# CFA_c.net
KiCad netlist of a schematic drawn in EAGLE
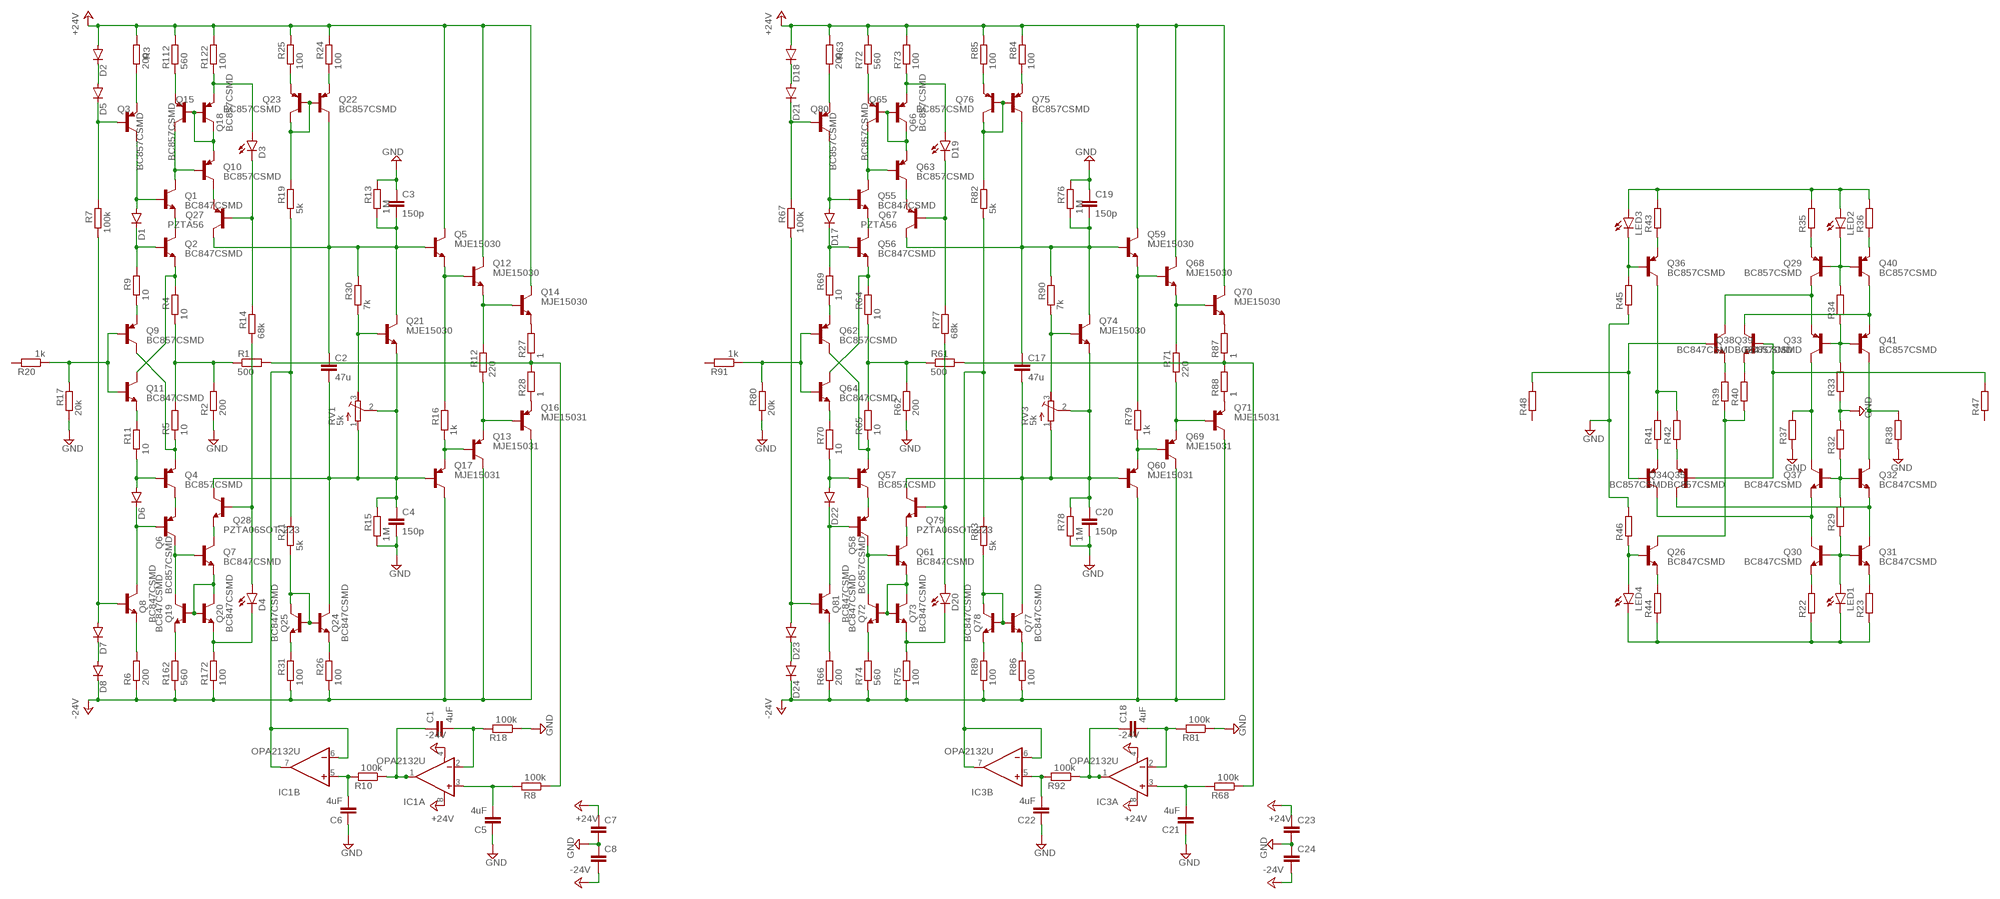
[diagram p0: schematic, sheet 1]

(export (version "E")
  (design (tool "Eeschema 10.0.6"))
  (components
    (comp (ref "C1")
      (value "4uF")
      (footprint "eagle-import:C1210")
      (fields (field (name "SPICEPREFIX") "C"))
      (libsource (lib "eagle-import") (part "C-EUC1210"))
    )
    (comp (ref "C2")
      (value "47u")
      (footprint "eagle-import:C1210")
      (fields (field (name "SPICEPREFIX") "C"))
      (libsource (lib "eagle-import") (part "C-EUC1210"))
    )
    (comp (ref "C3")
      (value "150p")
      (footprint "eagle-import:C0805")
      (fields (field (name "SPICEPREFIX") "C"))
      (libsource (lib "eagle-import") (part "C-EUC0805"))
    )
    (comp (ref "C4")
      (value "150p")
      (footprint "eagle-import:C0805")
      (fields (field (name "SPICEPREFIX") "C"))
      (libsource (lib "eagle-import") (part "C-EUC0805"))
    )
    (comp (ref "C5")
      (value "4uF")
      (footprint "eagle-import:C1210")
      (fields (field (name "SPICEPREFIX") "C"))
      (libsource (lib "eagle-import") (part "C-EUC1210"))
    )
    (comp (ref "C6")
      (value "4uF")
      (footprint "eagle-import:C1210")
      (fields (field (name "SPICEPREFIX") "C"))
      (libsource (lib "eagle-import") (part "C-EUC1210"))
    )
    (comp (ref "C7")
      (value "C-EUC0603K")
      (footprint "eagle-import:C0603K")
      (libsource (lib "eagle-import") (part "C-EUC0603K"))
    )
    (comp (ref "C8")
      (value "C-EUC0603K")
      (footprint "eagle-import:C0603K")
      (libsource (lib "eagle-import") (part "C-EUC0603K"))
    )
    (comp (ref "C17")
      (value "47u")
      (footprint "eagle-import:C1210")
      (fields (field (name "SPICEPREFIX") "C"))
      (libsource (lib "eagle-import") (part "C-EUC1210"))
    )
    (comp (ref "C18")
      (value "4uF")
      (footprint "eagle-import:C1210")
      (fields (field (name "SPICEPREFIX") "C"))
      (libsource (lib "eagle-import") (part "C-EUC1210"))
    )
    (comp (ref "C19")
      (value "150p")
      (footprint "eagle-import:C0805")
      (fields (field (name "SPICEPREFIX") "C"))
      (libsource (lib "eagle-import") (part "C-EUC0805"))
    )
    (comp (ref "C20")
      (value "150p")
      (footprint "eagle-import:C0805")
      (fields (field (name "SPICEPREFIX") "C"))
      (libsource (lib "eagle-import") (part "C-EUC0805"))
    )
    (comp (ref "C21")
      (value "4uF")
      (footprint "eagle-import:C1210")
      (fields (field (name "SPICEPREFIX") "C"))
      (libsource (lib "eagle-import") (part "C-EUC1210"))
    )
    (comp (ref "C22")
      (value "4uF")
      (footprint "eagle-import:C1210")
      (fields (field (name "SPICEPREFIX") "C"))
      (libsource (lib "eagle-import") (part "C-EUC1210"))
    )
    (comp (ref "C23")
      (value "C-EUC0603K")
      (footprint "eagle-import:C0603K")
      (libsource (lib "eagle-import") (part "C-EUC0603K"))
    )
    (comp (ref "C24")
      (value "C-EUC0603K")
      (footprint "eagle-import:C0603K")
      (libsource (lib "eagle-import") (part "C-EUC0603K"))
    )
    (comp (ref "D1")
      (value "DIODE-SOD80C")
      (footprint "eagle-import:SOD80C")
      (fields (field (name "SPICEPREFIX") "D"))
      (libsource (lib "eagle-import") (part "DIODE-SOD80C"))
    )
    (comp (ref "D2")
      (value "DIODE-SOD80C")
      (footprint "eagle-import:SOD80C")
      (fields (field (name "SPICEPREFIX") "D"))
      (libsource (lib "eagle-import") (part "DIODE-SOD80C"))
    )
    (comp (ref "D3")
      (value "LEDCHIPLED_1206")
      (footprint "eagle-import:CHIPLED_1206")
      (fields (field (name "SPICEPREFIX") "D"))
      (libsource (lib "eagle-import") (part "LEDCHIPLED_1206"))
    )
    (comp (ref "D4")
      (value "LEDCHIPLED_1206")
      (footprint "eagle-import:CHIPLED_1206")
      (fields (field (name "SPICEPREFIX") "D"))
      (libsource (lib "eagle-import") (part "LEDCHIPLED_1206"))
    )
    (comp (ref "D5")
      (value "DIODE-SOD80C")
      (footprint "eagle-import:SOD80C")
      (fields (field (name "SPICEPREFIX") "D"))
      (libsource (lib "eagle-import") (part "DIODE-SOD80C"))
    )
    (comp (ref "D6")
      (value "DIODE-SOD80C")
      (footprint "eagle-import:SOD80C")
      (fields (field (name "SPICEPREFIX") "D"))
      (libsource (lib "eagle-import") (part "DIODE-SOD80C"))
    )
    (comp (ref "D7")
      (value "DIODE-SOD80C")
      (footprint "eagle-import:SOD80C")
      (fields (field (name "SPICEPREFIX") "D"))
      (libsource (lib "eagle-import") (part "DIODE-SOD80C"))
    )
    (comp (ref "D8")
      (value "DIODE-SOD80C")
      (footprint "eagle-import:SOD80C")
      (fields (field (name "SPICEPREFIX") "D"))
      (libsource (lib "eagle-import") (part "DIODE-SOD80C"))
    )
    (comp (ref "D17")
      (value "DIODE-SOD80C")
      (footprint "eagle-import:SOD80C")
      (fields (field (name "SPICEPREFIX") "D"))
      (libsource (lib "eagle-import") (part "DIODE-SOD80C"))
    )
    (comp (ref "D18")
      (value "DIODE-SOD80C")
      (footprint "eagle-import:SOD80C")
      (fields (field (name "SPICEPREFIX") "D"))
      (libsource (lib "eagle-import") (part "DIODE-SOD80C"))
    )
    (comp (ref "D19")
      (value "LEDCHIPLED_1206")
      (footprint "eagle-import:CHIPLED_1206")
      (fields (field (name "SPICEPREFIX") "D"))
      (libsource (lib "eagle-import") (part "LEDCHIPLED_1206"))
    )
    (comp (ref "D20")
      (value "LEDCHIPLED_1206")
      (footprint "eagle-import:CHIPLED_1206")
      (fields (field (name "SPICEPREFIX") "D"))
      (libsource (lib "eagle-import") (part "LEDCHIPLED_1206"))
    )
    (comp (ref "D21")
      (value "DIODE-SOD80C")
      (footprint "eagle-import:SOD80C")
      (fields (field (name "SPICEPREFIX") "D"))
      (libsource (lib "eagle-import") (part "DIODE-SOD80C"))
    )
    (comp (ref "D22")
      (value "DIODE-SOD80C")
      (footprint "eagle-import:SOD80C")
      (fields (field (name "SPICEPREFIX") "D"))
      (libsource (lib "eagle-import") (part "DIODE-SOD80C"))
    )
    (comp (ref "D23")
      (value "DIODE-SOD80C")
      (footprint "eagle-import:SOD80C")
      (fields (field (name "SPICEPREFIX") "D"))
      (libsource (lib "eagle-import") (part "DIODE-SOD80C"))
    )
    (comp (ref "D24")
      (value "DIODE-SOD80C")
      (footprint "eagle-import:SOD80C")
      (fields (field (name "SPICEPREFIX") "D"))
      (libsource (lib "eagle-import") (part "DIODE-SOD80C"))
    )
    (comp (ref "IC1")
      (value "OPA2132U")
      (footprint "eagle-import:SO08")
      (fields (field (name "MF") "TEXAS INSTRUMENTS"))
      (libsource (lib "eagle-import") (part "OPA2132U"))
    )
    (comp (ref "IC3")
      (value "OPA2132U")
      (footprint "eagle-import:SO08")
      (fields (field (name "MF") "TEXAS INSTRUMENTS"))
      (libsource (lib "eagle-import") (part "OPA2132U"))
    )
    (comp (ref "LED1")
      (value "LEDCHIPLED_1206")
      (footprint "eagle-import:CHIPLED_1206")
      (libsource (lib "eagle-import") (part "LEDCHIPLED_1206"))
    )
    (comp (ref "LED2")
      (value "LEDCHIPLED_1206")
      (footprint "eagle-import:CHIPLED_1206")
      (libsource (lib "eagle-import") (part "LEDCHIPLED_1206"))
    )
    (comp (ref "LED3")
      (value "LEDCHIPLED_1206")
      (footprint "eagle-import:CHIPLED_1206")
      (libsource (lib "eagle-import") (part "LEDCHIPLED_1206"))
    )
    (comp (ref "LED4")
      (value "LEDCHIPLED_1206")
      (footprint "eagle-import:CHIPLED_1206")
      (fields (field (name "SPICEPREFIX") "D"))
      (libsource (lib "eagle-import") (part "LEDCHIPLED_1206"))
    )
    (comp (ref "Q1")
      (value "BC847CSMD")
      (footprint "eagle-import:SOT23")
      (fields (field (name "SPICEPREFIX") "Q"))
      (libsource (lib "eagle-import") (part "BC847SMDC"))
    )
    (comp (ref "Q2")
      (value "BC847CSMD")
      (footprint "eagle-import:SOT23")
      (fields (field (name "SPICEPREFIX") "Q"))
      (libsource (lib "eagle-import") (part "BC847SMDC"))
    )
    (comp (ref "Q3")
      (value "BC857CSMD")
      (footprint "eagle-import:SOT23-BEC")
      (fields (field (name "SPICEPREFIX") "Q"))
      (libsource (lib "eagle-import") (part "BC857SMDC"))
    )
    (comp (ref "Q4")
      (value "BC857CSMD")
      (footprint "eagle-import:SOT23-BEC")
      (fields (field (name "SPICEPREFIX") "Q"))
      (libsource (lib "eagle-import") (part "BC857SMDC"))
    )
    (comp (ref "Q5")
      (value "MJE15030")
      (footprint "eagle-import:DPAK")
      (fields (field (name "SPICEPREFIX") "Q"))
      (libsource (lib "eagle-import") (part "MJD31C"))
    )
    (comp (ref "Q6")
      (value "BC857CSMD")
      (footprint "eagle-import:SOT23-BEC")
      (fields (field (name "SPICEPREFIX") "Q"))
      (libsource (lib "eagle-import") (part "BC857SMDC"))
    )
    (comp (ref "Q7")
      (value "BC847CSMD")
      (footprint "eagle-import:SOT23")
      (fields (field (name "SPICEPREFIX") "Q"))
      (libsource (lib "eagle-import") (part "BC847SMDC"))
    )
    (comp (ref "Q8")
      (value "BC847CSMD")
      (footprint "eagle-import:SOT23")
      (fields (field (name "SPICEPREFIX") "Q"))
      (libsource (lib "eagle-import") (part "BC847SMDC"))
    )
    (comp (ref "Q9")
      (value "BC857CSMD")
      (footprint "eagle-import:SOT23-BEC")
      (fields (field (name "SPICEPREFIX") "Q"))
      (libsource (lib "eagle-import") (part "BC857SMDC"))
    )
    (comp (ref "Q10")
      (value "BC857CSMD")
      (footprint "eagle-import:SOT23-BEC")
      (fields (field (name "SPICEPREFIX") "Q"))
      (libsource (lib "eagle-import") (part "BC857SMDC"))
    )
    (comp (ref "Q11")
      (value "BC847CSMD")
      (footprint "eagle-import:SOT23")
      (fields (field (name "SPICEPREFIX") "Q"))
      (libsource (lib "eagle-import") (part "BC847SMDC"))
    )
    (comp (ref "Q12")
      (value "MJE15030")
      (footprint "eagle-import:DPAK")
      (fields (field (name "SPICEPREFIX") "Q"))
      (libsource (lib "eagle-import") (part "MJD31C"))
    )
    (comp (ref "Q13")
      (value "MJE15031")
      (footprint "eagle-import:DPAK")
      (fields (field (name "SPICEPREFIX") "Q"))
      (libsource (lib "eagle-import") (part "MJD32C"))
    )
    (comp (ref "Q14")
      (value "MJE15030")
      (footprint "eagle-import:DPAK")
      (fields (field (name "SPICEPREFIX") "Q"))
      (libsource (lib "eagle-import") (part "MJD31C"))
    )
    (comp (ref "Q15")
      (value "BC857CSMD")
      (footprint "eagle-import:SOT23-BEC")
      (fields (field (name "SPICEPREFIX") "Q"))
      (libsource (lib "eagle-import") (part "BC857SMDC"))
    )
    (comp (ref "Q16")
      (value "MJE15031")
      (footprint "eagle-import:DPAK")
      (fields (field (name "SPICEPREFIX") "Q"))
      (libsource (lib "eagle-import") (part "MJD32C"))
    )
    (comp (ref "Q17")
      (value "MJE15031")
      (footprint "eagle-import:DPAK")
      (fields (field (name "SPICEPREFIX") "Q"))
      (libsource (lib "eagle-import") (part "MJD32C"))
    )
    (comp (ref "Q18")
      (value "BC857CSMD")
      (footprint "eagle-import:SOT23-BEC")
      (fields (field (name "SPICEPREFIX") "Q"))
      (libsource (lib "eagle-import") (part "BC857SMDC"))
    )
    (comp (ref "Q19")
      (value "BC847CSMD")
      (footprint "eagle-import:SOT23")
      (fields (field (name "SPICEPREFIX") "Q"))
      (libsource (lib "eagle-import") (part "BC847SMDC"))
    )
    (comp (ref "Q20")
      (value "BC847CSMD")
      (footprint "eagle-import:SOT23")
      (fields (field (name "SPICEPREFIX") "Q"))
      (libsource (lib "eagle-import") (part "BC847SMDC"))
    )
    (comp (ref "Q21")
      (value "MJE15030")
      (footprint "eagle-import:DPAK")
      (fields (field (name "SPICEPREFIX") "Q"))
      (libsource (lib "eagle-import") (part "MJD31C"))
    )
    (comp (ref "Q22")
      (value "BC857CSMD")
      (footprint "eagle-import:SOT23-BEC")
      (fields (field (name "SPICEPREFIX") "Q"))
      (libsource (lib "eagle-import") (part "BC857SMDC"))
    )
    (comp (ref "Q23")
      (value "BC857CSMD")
      (footprint "eagle-import:SOT23-BEC")
      (fields (field (name "SPICEPREFIX") "Q"))
      (libsource (lib "eagle-import") (part "BC857SMDC"))
    )
    (comp (ref "Q24")
      (value "BC847CSMD")
      (footprint "eagle-import:SOT23")
      (fields (field (name "SPICEPREFIX") "Q"))
      (libsource (lib "eagle-import") (part "BC847SMDC"))
    )
    (comp (ref "Q25")
      (value "BC847CSMD")
      (footprint "eagle-import:SOT23")
      (fields (field (name "SPICEPREFIX") "Q"))
      (libsource (lib "eagle-import") (part "BC847SMDC"))
    )
    (comp (ref "Q26")
      (value "BC847CSMD")
      (footprint "eagle-import:SOT23")
      (fields (field (name "SPICEPREFIX") "Q"))
      (libsource (lib "eagle-import") (part "BC847SMDC"))
    )
    (comp (ref "Q27")
      (value "PZTA56")
      (footprint "eagle-import:SOT223")
      (fields (field (name "SPICEPREFIX") "Q"))
      (libsource (lib "eagle-import") (part "PZTA56"))
    )
    (comp (ref "Q28")
      (value "PZTA06SOT-223")
      (footprint "eagle-import:SOT223")
      (fields (field (name "SPICEPREFIX") "Q"))
      (libsource (lib "eagle-import") (part "PZTA06SOT-223"))
    )
    (comp (ref "Q29")
      (value "BC857CSMD")
      (footprint "eagle-import:SOT23-BEC")
      (fields (field (name "SPICEPREFIX") "Q"))
      (libsource (lib "eagle-import") (part "BC857SMDC"))
    )
    (comp (ref "Q30")
      (value "BC847CSMD")
      (footprint "eagle-import:SOT23")
      (fields (field (name "SPICEPREFIX") "Q"))
      (libsource (lib "eagle-import") (part "BC847SMDC"))
    )
    (comp (ref "Q31")
      (value "BC847CSMD")
      (footprint "eagle-import:SOT23")
      (fields (field (name "SPICEPREFIX") "Q"))
      (libsource (lib "eagle-import") (part "BC847SMDC"))
    )
    (comp (ref "Q32")
      (value "BC847CSMD")
      (footprint "eagle-import:SOT23")
      (fields (field (name "SPICEPREFIX") "Q"))
      (libsource (lib "eagle-import") (part "BC847SMDC"))
    )
    (comp (ref "Q33")
      (value "BC857CSMD")
      (footprint "eagle-import:SOT23-BEC")
      (fields (field (name "SPICEPREFIX") "Q"))
      (libsource (lib "eagle-import") (part "BC857SMDC"))
    )
    (comp (ref "Q34")
      (value "BC857CSMD")
      (footprint "eagle-import:SOT23-BEC")
      (fields (field (name "SPICEPREFIX") "Q"))
      (libsource (lib "eagle-import") (part "BC857SMDC"))
    )
    (comp (ref "Q35")
      (value "BC857CSMD")
      (footprint "eagle-import:SOT23-BEC")
      (fields (field (name "SPICEPREFIX") "Q"))
      (libsource (lib "eagle-import") (part "BC857SMDC"))
    )
    (comp (ref "Q36")
      (value "BC857CSMD")
      (footprint "eagle-import:SOT23-BEC")
      (fields (field (name "SPICEPREFIX") "Q"))
      (libsource (lib "eagle-import") (part "BC857SMDC"))
    )
    (comp (ref "Q37")
      (value "BC847CSMD")
      (footprint "eagle-import:SOT23")
      (fields (field (name "SPICEPREFIX") "Q"))
      (libsource (lib "eagle-import") (part "BC847SMDC"))
    )
    (comp (ref "Q38")
      (value "BC847CSMD")
      (footprint "eagle-import:SOT23")
      (fields (field (name "SPICEPREFIX") "Q"))
      (libsource (lib "eagle-import") (part "BC847SMDC"))
    )
    (comp (ref "Q39")
      (value "BC847CSMD")
      (footprint "eagle-import:SOT23")
      (fields (field (name "SPICEPREFIX") "Q"))
      (libsource (lib "eagle-import") (part "BC847SMDC"))
    )
    (comp (ref "Q40")
      (value "BC857CSMD")
      (footprint "eagle-import:SOT23-BEC")
      (fields (field (name "SPICEPREFIX") "Q"))
      (libsource (lib "eagle-import") (part "BC857SMDC"))
    )
    (comp (ref "Q41")
      (value "BC857CSMD")
      (footprint "eagle-import:SOT23-BEC")
      (fields (field (name "SPICEPREFIX") "Q"))
      (libsource (lib "eagle-import") (part "BC857SMDC"))
    )
    (comp (ref "Q55")
      (value "BC847CSMD")
      (footprint "eagle-import:SOT23")
      (fields (field (name "SPICEPREFIX") "Q"))
      (libsource (lib "eagle-import") (part "BC847SMDC"))
    )
    (comp (ref "Q56")
      (value "BC847CSMD")
      (footprint "eagle-import:SOT23")
      (fields (field (name "SPICEPREFIX") "Q"))
      (libsource (lib "eagle-import") (part "BC847SMDC"))
    )
    (comp (ref "Q57")
      (value "BC857CSMD")
      (footprint "eagle-import:SOT23-BEC")
      (fields (field (name "SPICEPREFIX") "Q"))
      (libsource (lib "eagle-import") (part "BC857SMDC"))
    )
    (comp (ref "Q58")
      (value "BC857CSMD")
      (footprint "eagle-import:SOT23-BEC")
      (fields (field (name "SPICEPREFIX") "Q"))
      (libsource (lib "eagle-import") (part "BC857SMDC"))
    )
    (comp (ref "Q59")
      (value "MJE15030")
      (footprint "eagle-import:DPAK")
      (fields (field (name "SPICEPREFIX") "Q"))
      (libsource (lib "eagle-import") (part "MJD31C"))
    )
    (comp (ref "Q60")
      (value "MJE15031")
      (footprint "eagle-import:DPAK")
      (fields (field (name "SPICEPREFIX") "Q"))
      (libsource (lib "eagle-import") (part "MJD32C"))
    )
    (comp (ref "Q61")
      (value "BC847CSMD")
      (footprint "eagle-import:SOT23")
      (fields (field (name "SPICEPREFIX") "Q"))
      (libsource (lib "eagle-import") (part "BC847SMDC"))
    )
    (comp (ref "Q62")
      (value "BC857CSMD")
      (footprint "eagle-import:SOT23-BEC")
      (fields (field (name "SPICEPREFIX") "Q"))
      (libsource (lib "eagle-import") (part "BC857SMDC"))
    )
    (comp (ref "Q63")
      (value "BC857CSMD")
      (footprint "eagle-import:SOT23-BEC")
      (fields (field (name "SPICEPREFIX") "Q"))
      (libsource (lib "eagle-import") (part "BC857SMDC"))
    )
    (comp (ref "Q64")
      (value "BC847CSMD")
      (footprint "eagle-import:SOT23")
      (fields (field (name "SPICEPREFIX") "Q"))
      (libsource (lib "eagle-import") (part "BC847SMDC"))
    )
    (comp (ref "Q65")
      (value "BC857CSMD")
      (footprint "eagle-import:SOT23-BEC")
      (fields (field (name "SPICEPREFIX") "Q"))
      (libsource (lib "eagle-import") (part "BC857SMDC"))
    )
    (comp (ref "Q66")
      (value "BC857CSMD")
      (footprint "eagle-import:SOT23-BEC")
      (fields (field (name "SPICEPREFIX") "Q"))
      (libsource (lib "eagle-import") (part "BC857SMDC"))
    )
    (comp (ref "Q67")
      (value "PZTA56")
      (footprint "eagle-import:SOT223")
      (fields (field (name "SPICEPREFIX") "Q"))
      (libsource (lib "eagle-import") (part "PZTA56"))
    )
    (comp (ref "Q68")
      (value "MJE15030")
      (footprint "eagle-import:DPAK")
      (fields (field (name "SPICEPREFIX") "Q"))
      (libsource (lib "eagle-import") (part "MJD31C"))
    )
    (comp (ref "Q69")
      (value "MJE15031")
      (footprint "eagle-import:DPAK")
      (fields (field (name "SPICEPREFIX") "Q"))
      (libsource (lib "eagle-import") (part "MJD32C"))
    )
    (comp (ref "Q70")
      (value "MJE15030")
      (footprint "eagle-import:DPAK")
      (fields (field (name "SPICEPREFIX") "Q"))
      (libsource (lib "eagle-import") (part "MJD31C"))
    )
    (comp (ref "Q71")
      (value "MJE15031")
      (footprint "eagle-import:DPAK")
      (fields (field (name "SPICEPREFIX") "Q"))
      (libsource (lib "eagle-import") (part "MJD32C"))
    )
    (comp (ref "Q72")
      (value "BC847CSMD")
      (footprint "eagle-import:SOT23")
      (fields (field (name "SPICEPREFIX") "Q"))
      (libsource (lib "eagle-import") (part "BC847SMDC"))
    )
    (comp (ref "Q73")
      (value "BC847CSMD")
      (footprint "eagle-import:SOT23")
      (fields (field (name "SPICEPREFIX") "Q"))
      (libsource (lib "eagle-import") (part "BC847SMDC"))
    )
    (comp (ref "Q74")
      (value "MJE15030")
      (footprint "eagle-import:DPAK")
      (fields (field (name "SPICEPREFIX") "Q"))
      (libsource (lib "eagle-import") (part "MJD31C"))
    )
    (comp (ref "Q75")
      (value "BC857CSMD")
      (footprint "eagle-import:SOT23-BEC")
      (fields (field (name "SPICEPREFIX") "Q"))
      (libsource (lib "eagle-import") (part "BC857SMDC"))
    )
    (comp (ref "Q76")
      (value "BC857CSMD")
      (footprint "eagle-import:SOT23-BEC")
      (fields (field (name "SPICEPREFIX") "Q"))
      (libsource (lib "eagle-import") (part "BC857SMDC"))
    )
    (comp (ref "Q77")
      (value "BC847CSMD")
      (footprint "eagle-import:SOT23")
      (fields (field (name "SPICEPREFIX") "Q"))
      (libsource (lib "eagle-import") (part "BC847SMDC"))
    )
    (comp (ref "Q78")
      (value "BC847CSMD")
      (footprint "eagle-import:SOT23")
      (fields (field (name "SPICEPREFIX") "Q"))
      (libsource (lib "eagle-import") (part "BC847SMDC"))
    )
    (comp (ref "Q79")
      (value "PZTA06SOT-223")
      (footprint "eagle-import:SOT223")
      (fields (field (name "SPICEPREFIX") "Q"))
      (libsource (lib "eagle-import") (part "PZTA06SOT-223"))
    )
    (comp (ref "Q80")
      (value "BC857CSMD")
      (footprint "eagle-import:SOT23-BEC")
      (fields (field (name "SPICEPREFIX") "Q"))
      (libsource (lib "eagle-import") (part "BC857SMDC"))
    )
    (comp (ref "Q81")
      (value "BC847CSMD")
      (footprint "eagle-import:SOT23")
      (fields (field (name "SPICEPREFIX") "Q"))
      (libsource (lib "eagle-import") (part "BC847SMDC"))
    )
    (comp (ref "R1")
      (value "500")
      (footprint "eagle-import:MINI_MELF-0204W")
      (fields (field (name "SPICEPREFIX") "R"))
      (libsource (lib "eagle-import") (part "R-EU_MELF0204W"))
    )
    (comp (ref "R2")
      (value "200")
      (footprint "eagle-import:MINI_MELF-0204W")
      (fields (field (name "SPICEPREFIX") "R"))
      (libsource (lib "eagle-import") (part "R-EU_MELF0204W"))
    )
    (comp (ref "R3")
      (value "200")
      (footprint "eagle-import:MINI_MELF-0204W")
      (fields (field (name "SPICEPREFIX") "R"))
      (libsource (lib "eagle-import") (part "R-EU_MELF0204W"))
    )
    (comp (ref "R4")
      (value "10")
      (footprint "eagle-import:MINI_MELF-0204W")
      (fields (field (name "SPICEPREFIX") "R"))
      (libsource (lib "eagle-import") (part "R-EU_MELF0204W"))
    )
    (comp (ref "R5")
      (value "10")
      (footprint "eagle-import:MINI_MELF-0204W")
      (fields (field (name "SPICEPREFIX") "R"))
      (libsource (lib "eagle-import") (part "R-EU_MELF0204W"))
    )
    (comp (ref "R6")
      (value "200")
      (footprint "eagle-import:MINI_MELF-0204W")
      (fields (field (name "SPICEPREFIX") "R"))
      (libsource (lib "eagle-import") (part "R-EU_MELF0204W"))
    )
    (comp (ref "R7")
      (value "100k")
      (footprint "eagle-import:MINI_MELF-0204W")
      (fields (field (name "SPICEPREFIX") "R"))
      (libsource (lib "eagle-import") (part "R-EU_MELF0204W"))
    )
    (comp (ref "R8")
      (value "100k")
      (footprint "eagle-import:MINI_MELF-0204W")
      (fields (field (name "SPICEPREFIX") "R"))
      (libsource (lib "eagle-import") (part "R-EU_MELF0204W"))
    )
    (comp (ref "R9")
      (value "10")
      (footprint "eagle-import:MINI_MELF-0204W")
      (fields (field (name "SPICEPREFIX") "R"))
      (libsource (lib "eagle-import") (part "R-EU_MELF0204W"))
    )
    (comp (ref "R10")
      (value "100k")
      (footprint "eagle-import:MINI_MELF-0204W")
      (fields (field (name "SPICEPREFIX") "R"))
      (libsource (lib "eagle-import") (part "R-EU_MELF0204W"))
    )
    (comp (ref "R11")
      (value "10")
      (footprint "eagle-import:MINI_MELF-0204W")
      (fields (field (name "SPICEPREFIX") "R"))
      (libsource (lib "eagle-import") (part "R-EU_MELF0204W"))
    )
    (comp (ref "R12")
      (value "220")
      (footprint "eagle-import:MINI_MELF-0204W")
      (fields (field (name "SPICEPREFIX") "R"))
      (libsource (lib "eagle-import") (part "R-EU_MELF0204W"))
    )
    (comp (ref "R13")
      (value "1M")
      (footprint "eagle-import:MINI_MELF-0204W")
      (fields (field (name "SPICEPREFIX") "R"))
      (libsource (lib "eagle-import") (part "R-EU_MELF0204W"))
    )
    (comp (ref "R14")
      (value "68k")
      (footprint "eagle-import:MINI_MELF-0204W")
      (fields (field (name "SPICEPREFIX") "R"))
      (libsource (lib "eagle-import") (part "R-EU_MELF0204W"))
    )
    (comp (ref "R15")
      (value "1M")
      (footprint "eagle-import:MINI_MELF-0204W")
      (fields (field (name "SPICEPREFIX") "R"))
      (libsource (lib "eagle-import") (part "R-EU_MELF0204W"))
    )
    (comp (ref "R16")
      (value "1k")
      (footprint "eagle-import:MINI_MELF-0204W")
      (fields (field (name "SPICEPREFIX") "R"))
      (libsource (lib "eagle-import") (part "R-EU_MELF0204W"))
    )
    (comp (ref "R17")
      (value "20k")
      (footprint "eagle-import:MINI_MELF-0204W")
      (fields (field (name "SPICEPREFIX") "R"))
      (libsource (lib "eagle-import") (part "R-EU_MELF0204W"))
    )
    (comp (ref "R18")
      (value "100k")
      (footprint "eagle-import:MINI_MELF-0204W")
      (fields (field (name "SPICEPREFIX") "R"))
      (libsource (lib "eagle-import") (part "R-EU_MELF0204W"))
    )
    (comp (ref "R19")
      (value "5k")
      (footprint "eagle-import:MINI_MELF-0204W")
      (fields (field (name "SPICEPREFIX") "R"))
      (libsource (lib "eagle-import") (part "R-EU_MELF0204W"))
    )
    (comp (ref "R20")
      (value "1k")
      (footprint "eagle-import:MINI_MELF-0204W")
      (fields (field (name "SPICEPREFIX") "R"))
      (libsource (lib "eagle-import") (part "R-EU_MELF0204W"))
    )
    (comp (ref "R21")
      (value "5k")
      (footprint "eagle-import:MINI_MELF-0204W")
      (fields (field (name "SPICEPREFIX") "R"))
      (libsource (lib "eagle-import") (part "R-EU_MELF0204W"))
    )
    (comp (ref "R22")
      (value "R-EU_MELF0204W")
      (footprint "eagle-import:MINI_MELF-0204W")
      (libsource (lib "eagle-import") (part "R-EU_MELF0204W"))
    )
    (comp (ref "R23")
      (value "R-EU_MELF0204W")
      (footprint "eagle-import:MINI_MELF-0204W")
      (libsource (lib "eagle-import") (part "R-EU_MELF0204W"))
    )
    (comp (ref "R24")
      (value "100")
      (footprint "eagle-import:MINI_MELF-0204W")
      (fields (field (name "SPICEPREFIX") "R"))
      (libsource (lib "eagle-import") (part "R-EU_MELF0204W"))
    )
    (comp (ref "R25")
      (value "100")
      (footprint "eagle-import:MINI_MELF-0204W")
      (fields (field (name "SPICEPREFIX") "R"))
      (libsource (lib "eagle-import") (part "R-EU_MELF0204W"))
    )
    (comp (ref "R26")
      (value "100")
      (footprint "eagle-import:MINI_MELF-0204W")
      (fields (field (name "SPICEPREFIX") "R"))
      (libsource (lib "eagle-import") (part "R-EU_MELF0204W"))
    )
    (comp (ref "R27")
      (value "1")
      (footprint "eagle-import:R4527")
      (fields (field (name "SPICEPREFIX") "R"))
      (libsource (lib "eagle-import") (part "R-EU_R4527"))
    )
    (comp (ref "R28")
      (value "1")
      (footprint "eagle-import:R4527")
      (fields (field (name "SPICEPREFIX") "R"))
      (libsource (lib "eagle-import") (part "R-EU_R4527"))
    )
    (comp (ref "R29")
      (value "R-EU_MELF0204W")
      (footprint "eagle-import:MINI_MELF-0204W")
      (libsource (lib "eagle-import") (part "R-EU_MELF0204W"))
    )
    (comp (ref "R30")
      (value "7k")
      (footprint "eagle-import:MINI_MELF-0204W")
      (fields (field (name "SPICEPREFIX") "R"))
      (libsource (lib "eagle-import") (part "R-EU_MELF0204W"))
    )
    (comp (ref "R31")
      (value "100")
      (footprint "eagle-import:MINI_MELF-0204W")
      (fields (field (name "SPICEPREFIX") "R"))
      (libsource (lib "eagle-import") (part "R-EU_MELF0204W"))
    )
    (comp (ref "R32")
      (value "R-EU_MELF0204W")
      (footprint "eagle-import:MINI_MELF-0204W")
      (libsource (lib "eagle-import") (part "R-EU_MELF0204W"))
    )
    (comp (ref "R33")
      (value "R-EU_MELF0204W")
      (footprint "eagle-import:MINI_MELF-0204W")
      (libsource (lib "eagle-import") (part "R-EU_MELF0204W"))
    )
    (comp (ref "R34")
      (value "R-EU_MELF0204W")
      (footprint "eagle-import:MINI_MELF-0204W")
      (libsource (lib "eagle-import") (part "R-EU_MELF0204W"))
    )
    (comp (ref "R35")
      (value "R-EU_MELF0204W")
      (footprint "eagle-import:MINI_MELF-0204W")
      (libsource (lib "eagle-import") (part "R-EU_MELF0204W"))
    )
    (comp (ref "R36")
      (value "R-EU_MELF0204W")
      (footprint "eagle-import:MINI_MELF-0204W")
      (libsource (lib "eagle-import") (part "R-EU_MELF0204W"))
    )
    (comp (ref "R37")
      (value "R-EU_MELF0204W")
      (footprint "eagle-import:MINI_MELF-0204W")
      (libsource (lib "eagle-import") (part "R-EU_MELF0204W"))
    )
    (comp (ref "R38")
      (value "R-EU_MELF0204W")
      (footprint "eagle-import:MINI_MELF-0204W")
      (libsource (lib "eagle-import") (part "R-EU_MELF0204W"))
    )
    (comp (ref "R39")
      (value "R-EU_MELF0204W")
      (footprint "eagle-import:MINI_MELF-0204W")
      (libsource (lib "eagle-import") (part "R-EU_MELF0204W"))
    )
    (comp (ref "R40")
      (value "R-EU_MELF0204W")
      (footprint "eagle-import:MINI_MELF-0204W")
      (libsource (lib "eagle-import") (part "R-EU_MELF0204W"))
    )
    (comp (ref "R41")
      (value "R-EU_MELF0204W")
      (footprint "eagle-import:MINI_MELF-0204W")
      (libsource (lib "eagle-import") (part "R-EU_MELF0204W"))
    )
    (comp (ref "R42")
      (value "R-EU_MELF0204W")
      (footprint "eagle-import:MINI_MELF-0204W")
      (libsource (lib "eagle-import") (part "R-EU_MELF0204W"))
    )
    (comp (ref "R43")
      (value "R-EU_MELF0204W")
      (footprint "eagle-import:MINI_MELF-0204W")
      (libsource (lib "eagle-import") (part "R-EU_MELF0204W"))
    )
    (comp (ref "R44")
      (value "R-EU_MELF0204W")
      (footprint "eagle-import:MINI_MELF-0204W")
      (fields (field (name "SPICEPREFIX") "R"))
      (libsource (lib "eagle-import") (part "R-EU_MELF0204W"))
    )
    (comp (ref "R45")
      (value "R-EU_MELF0204W")
      (footprint "eagle-import:MINI_MELF-0204W")
      (libsource (lib "eagle-import") (part "R-EU_MELF0204W"))
    )
    (comp (ref "R46")
      (value "R-EU_MELF0204W")
      (footprint "eagle-import:MINI_MELF-0204W")
      (libsource (lib "eagle-import") (part "R-EU_MELF0204W"))
    )
    (comp (ref "R47")
      (value "R-EU_MELF0204W")
      (footprint "eagle-import:MINI_MELF-0204W")
      (libsource (lib "eagle-import") (part "R-EU_MELF0204W"))
    )
    (comp (ref "R48")
      (value "R-EU_MELF0204W")
      (footprint "eagle-import:MINI_MELF-0204W")
      (libsource (lib "eagle-import") (part "R-EU_MELF0204W"))
    )
    (comp (ref "R61")
      (value "500")
      (footprint "eagle-import:MINI_MELF-0204W")
      (fields (field (name "SPICEPREFIX") "R"))
      (libsource (lib "eagle-import") (part "R-EU_MELF0204W"))
    )
    (comp (ref "R62")
      (value "200")
      (footprint "eagle-import:MINI_MELF-0204W")
      (fields (field (name "SPICEPREFIX") "R"))
      (libsource (lib "eagle-import") (part "R-EU_MELF0204W"))
    )
    (comp (ref "R63")
      (value "200")
      (footprint "eagle-import:MINI_MELF-0204W")
      (fields (field (name "SPICEPREFIX") "R"))
      (libsource (lib "eagle-import") (part "R-EU_MELF0204W"))
    )
    (comp (ref "R64")
      (value "10")
      (footprint "eagle-import:MINI_MELF-0204W")
      (fields (field (name "SPICEPREFIX") "R"))
      (libsource (lib "eagle-import") (part "R-EU_MELF0204W"))
    )
    (comp (ref "R65")
      (value "10")
      (footprint "eagle-import:MINI_MELF-0204W")
      (fields (field (name "SPICEPREFIX") "R"))
      (libsource (lib "eagle-import") (part "R-EU_MELF0204W"))
    )
    (comp (ref "R66")
      (value "200")
      (footprint "eagle-import:MINI_MELF-0204W")
      (fields (field (name "SPICEPREFIX") "R"))
      (libsource (lib "eagle-import") (part "R-EU_MELF0204W"))
    )
    (comp (ref "R67")
      (value "100k")
      (footprint "eagle-import:MINI_MELF-0204W")
      (fields (field (name "SPICEPREFIX") "R"))
      (libsource (lib "eagle-import") (part "R-EU_MELF0204W"))
    )
    (comp (ref "R68")
      (value "100k")
      (footprint "eagle-import:MINI_MELF-0204W")
      (fields (field (name "SPICEPREFIX") "R"))
      (libsource (lib "eagle-import") (part "R-EU_MELF0204W"))
    )
    (comp (ref "R69")
      (value "10")
      (footprint "eagle-import:MINI_MELF-0204W")
      (fields (field (name "SPICEPREFIX") "R"))
      (libsource (lib "eagle-import") (part "R-EU_MELF0204W"))
    )
    (comp (ref "R70")
      (value "10")
      (footprint "eagle-import:MINI_MELF-0204W")
      (fields (field (name "SPICEPREFIX") "R"))
      (libsource (lib "eagle-import") (part "R-EU_MELF0204W"))
    )
    (comp (ref "R71")
      (value "220")
      (footprint "eagle-import:MINI_MELF-0204W")
      (fields (field (name "SPICEPREFIX") "R"))
      (libsource (lib "eagle-import") (part "R-EU_MELF0204W"))
    )
    (comp (ref "R72")
      (value "560")
      (footprint "eagle-import:MINI_MELF-0204W")
      (fields (field (name "SPICEPREFIX") "R"))
      (libsource (lib "eagle-import") (part "R-EU_MELF0204W"))
    )
    (comp (ref "R73")
      (value "100")
      (footprint "eagle-import:MINI_MELF-0204W")
      (fields (field (name "SPICEPREFIX") "R"))
      (libsource (lib "eagle-import") (part "R-EU_MELF0204W"))
    )
    (comp (ref "R74")
      (value "560")
      (footprint "eagle-import:MINI_MELF-0204W")
      (fields (field (name "SPICEPREFIX") "R"))
      (libsource (lib "eagle-import") (part "R-EU_MELF0204W"))
    )
    (comp (ref "R75")
      (value "100")
      (footprint "eagle-import:MINI_MELF-0204W")
      (fields (field (name "SPICEPREFIX") "R"))
      (libsource (lib "eagle-import") (part "R-EU_MELF0204W"))
    )
    (comp (ref "R76")
      (value "1M")
      (footprint "eagle-import:MINI_MELF-0204W")
      (fields (field (name "SPICEPREFIX") "R"))
      (libsource (lib "eagle-import") (part "R-EU_MELF0204W"))
    )
    (comp (ref "R77")
      (value "68k")
      (footprint "eagle-import:MINI_MELF-0204W")
      (fields (field (name "SPICEPREFIX") "R"))
      (libsource (lib "eagle-import") (part "R-EU_MELF0204W"))
    )
    (comp (ref "R78")
      (value "1M")
      (footprint "eagle-import:MINI_MELF-0204W")
      (fields (field (name "SPICEPREFIX") "R"))
      (libsource (lib "eagle-import") (part "R-EU_MELF0204W"))
    )
    (comp (ref "R79")
      (value "1k")
      (footprint "eagle-import:MINI_MELF-0204W")
      (fields (field (name "SPICEPREFIX") "R"))
      (libsource (lib "eagle-import") (part "R-EU_MELF0204W"))
    )
    (comp (ref "R80")
      (value "20k")
      (footprint "eagle-import:MINI_MELF-0204W")
      (fields (field (name "SPICEPREFIX") "R"))
      (libsource (lib "eagle-import") (part "R-EU_MELF0204W"))
    )
    (comp (ref "R81")
      (value "100k")
      (footprint "eagle-import:MINI_MELF-0204W")
      (fields (field (name "SPICEPREFIX") "R"))
      (libsource (lib "eagle-import") (part "R-EU_MELF0204W"))
    )
    (comp (ref "R82")
      (value "5k")
      (footprint "eagle-import:MINI_MELF-0204W")
      (fields (field (name "SPICEPREFIX") "R"))
      (libsource (lib "eagle-import") (part "R-EU_MELF0204W"))
    )
    (comp (ref "R83")
      (value "5k")
      (footprint "eagle-import:MINI_MELF-0204W")
      (fields (field (name "SPICEPREFIX") "R"))
      (libsource (lib "eagle-import") (part "R-EU_MELF0204W"))
    )
    (comp (ref "R84")
      (value "100")
      (footprint "eagle-import:MINI_MELF-0204W")
      (fields (field (name "SPICEPREFIX") "R"))
      (libsource (lib "eagle-import") (part "R-EU_MELF0204W"))
    )
    (comp (ref "R85")
      (value "100")
      (footprint "eagle-import:MINI_MELF-0204W")
      (fields (field (name "SPICEPREFIX") "R"))
      (libsource (lib "eagle-import") (part "R-EU_MELF0204W"))
    )
    (comp (ref "R86")
      (value "100")
      (footprint "eagle-import:MINI_MELF-0204W")
      (fields (field (name "SPICEPREFIX") "R"))
      (libsource (lib "eagle-import") (part "R-EU_MELF0204W"))
    )
    (comp (ref "R87")
      (value "1")
      (footprint "eagle-import:R4527")
      (fields (field (name "SPICEPREFIX") "R"))
      (libsource (lib "eagle-import") (part "R-EU_R4527"))
    )
    (comp (ref "R88")
      (value "1")
      (footprint "eagle-import:R4527")
      (fields (field (name "SPICEPREFIX") "R"))
      (libsource (lib "eagle-import") (part "R-EU_R4527"))
    )
    (comp (ref "R89")
      (value "100")
      (footprint "eagle-import:MINI_MELF-0204W")
      (fields (field (name "SPICEPREFIX") "R"))
      (libsource (lib "eagle-import") (part "R-EU_MELF0204W"))
    )
    (comp (ref "R90")
      (value "7k")
      (footprint "eagle-import:MINI_MELF-0204W")
      (fields (field (name "SPICEPREFIX") "R"))
      (libsource (lib "eagle-import") (part "R-EU_MELF0204W"))
    )
    (comp (ref "R91")
      (value "1k")
      (footprint "eagle-import:MINI_MELF-0204W")
      (fields (field (name "SPICEPREFIX") "R"))
      (libsource (lib "eagle-import") (part "R-EU_MELF0204W"))
    )
    (comp (ref "R92")
      (value "100k")
      (footprint "eagle-import:MINI_MELF-0204W")
      (fields (field (name "SPICEPREFIX") "R"))
      (libsource (lib "eagle-import") (part "R-EU_MELF0204W"))
    )
    (comp (ref "R112")
      (value "560")
      (footprint "eagle-import:MINI_MELF-0204W")
      (fields (field (name "SPICEPREFIX") "R"))
      (libsource (lib "eagle-import") (part "R-EU_MELF0204W"))
    )
    (comp (ref "R122")
      (value "100")
      (footprint "eagle-import:MINI_MELF-0204W")
      (fields (field (name "SPICEPREFIX") "R"))
      (libsource (lib "eagle-import") (part "R-EU_MELF0204W"))
    )
    (comp (ref "R162")
      (value "560")
      (footprint "eagle-import:MINI_MELF-0204W")
      (fields (field (name "SPICEPREFIX") "R"))
      (libsource (lib "eagle-import") (part "R-EU_MELF0204W"))
    )
    (comp (ref "R172")
      (value "100")
      (footprint "eagle-import:MINI_MELF-0204W")
      (fields (field (name "SPICEPREFIX") "R"))
      (libsource (lib "eagle-import") (part "R-EU_MELF0204W"))
    )
    (comp (ref "RV1")
      (value "5k")
      (footprint "eagle-import:RTRIMTS63Y")
      (fields (field (name "SPICEPREFIX") "Z"))
      (libsource (lib "eagle-import") (part "R-TRIMMTS63Y"))
    )
    (comp (ref "RV3")
      (value "5k")
      (footprint "eagle-import:RTRIMTS63Y")
      (fields (field (name "SPICEPREFIX") "Z"))
      (libsource (lib "eagle-import") (part "R-TRIMMTS63Y"))
    )
  )
  (nets
    (net (code "1") (name "+24V") (class "Default")
      (node (ref "C23") (pin "1") (pinfunction "1_1") (pintype "passive"))
      (node (ref "C7") (pin "1") (pinfunction "1_1") (pintype "passive"))
      (node (ref "D18") (pin "A") (pinfunction "A_A") (pintype "passive"))
      (node (ref "D2") (pin "A") (pinfunction "A_A") (pintype "passive"))
      (node (ref "IC1") (pin "8") (pinfunction "V+_8") (pintype "power_in"))
      (node (ref "IC3") (pin "8") (pinfunction "V+_8") (pintype "power_in"))
      (node (ref "Q12") (pin "4") (pinfunction "C_4") (pintype "passive"))
      (node (ref "Q14") (pin "4") (pinfunction "C_4") (pintype "passive"))
      (node (ref "Q5") (pin "4") (pinfunction "C_4") (pintype "passive"))
      (node (ref "Q59") (pin "4") (pinfunction "C_4") (pintype "passive"))
      (node (ref "Q68") (pin "4") (pinfunction "C_4") (pintype "passive"))
      (node (ref "Q70") (pin "4") (pinfunction "C_4") (pintype "passive"))
      (node (ref "R112") (pin "2") (pinfunction "2_2") (pintype "passive"))
      (node (ref "R122") (pin "2") (pinfunction "2_2") (pintype "passive"))
      (node (ref "R24") (pin "2") (pinfunction "2_2") (pintype "passive"))
      (node (ref "R25") (pin "2") (pinfunction "2_2") (pintype "passive"))
      (node (ref "R3") (pin "2") (pinfunction "2_2") (pintype "passive"))
      (node (ref "R63") (pin "2") (pinfunction "2_2") (pintype "passive"))
      (node (ref "R72") (pin "2") (pinfunction "2_2") (pintype "passive"))
      (node (ref "R73") (pin "2") (pinfunction "2_2") (pintype "passive"))
      (node (ref "R84") (pin "2") (pinfunction "2_2") (pintype "passive"))
      (node (ref "R85") (pin "2") (pinfunction "2_2") (pintype "passive"))
    )
    (net (code "2") (name "-24V") (class "Default")
      (node (ref "C24") (pin "2") (pinfunction "2_2") (pintype "passive"))
      (node (ref "C8") (pin "2") (pinfunction "2_2") (pintype "passive"))
      (node (ref "D24") (pin "C") (pinfunction "C_C") (pintype "passive"))
      (node (ref "D8") (pin "C") (pinfunction "C_C") (pintype "passive"))
      (node (ref "IC1") (pin "4") (pinfunction "V-_4") (pintype "power_in"))
      (node (ref "IC3") (pin "4") (pinfunction "V-_4") (pintype "power_in"))
      (node (ref "Q13") (pin "4") (pinfunction "C_4") (pintype "passive"))
      (node (ref "Q16") (pin "4") (pinfunction "C_4") (pintype "passive"))
      (node (ref "Q17") (pin "4") (pinfunction "C_4") (pintype "passive"))
      (node (ref "Q60") (pin "4") (pinfunction "C_4") (pintype "passive"))
      (node (ref "Q69") (pin "4") (pinfunction "C_4") (pintype "passive"))
      (node (ref "Q71") (pin "4") (pinfunction "C_4") (pintype "passive"))
      (node (ref "R162") (pin "1") (pinfunction "1_1") (pintype "passive"))
      (node (ref "R172") (pin "1") (pinfunction "1_1") (pintype "passive"))
      (node (ref "R26") (pin "1") (pinfunction "1_1") (pintype "passive"))
      (node (ref "R31") (pin "1") (pinfunction "1_1") (pintype "passive"))
      (node (ref "R6") (pin "1") (pinfunction "1_1") (pintype "passive"))
      (node (ref "R66") (pin "1") (pinfunction "1_1") (pintype "passive"))
      (node (ref "R74") (pin "1") (pinfunction "1_1") (pintype "passive"))
      (node (ref "R75") (pin "1") (pinfunction "1_1") (pintype "passive"))
      (node (ref "R86") (pin "1") (pinfunction "1_1") (pintype "passive"))
      (node (ref "R89") (pin "1") (pinfunction "1_1") (pintype "passive"))
    )
    (net (code "3") (name "GND") (class "Default")
      (node (ref "C19") (pin "1") (pinfunction "1_1") (pintype "passive"))
      (node (ref "C20") (pin "2") (pinfunction "2_2") (pintype "passive"))
      (node (ref "C21") (pin "1") (pinfunction "1_1") (pintype "passive"))
      (node (ref "C22") (pin "1") (pinfunction "1_1") (pintype "passive"))
      (node (ref "C23") (pin "2") (pinfunction "2_2") (pintype "passive"))
      (node (ref "C24") (pin "1") (pinfunction "1_1") (pintype "passive"))
      (node (ref "C3") (pin "1") (pinfunction "1_1") (pintype "passive"))
      (node (ref "C4") (pin "2") (pinfunction "2_2") (pintype "passive"))
      (node (ref "C5") (pin "1") (pinfunction "1_1") (pintype "passive"))
      (node (ref "C6") (pin "1") (pinfunction "1_1") (pintype "passive"))
      (node (ref "C7") (pin "2") (pinfunction "2_2") (pintype "passive"))
      (node (ref "C8") (pin "1") (pinfunction "1_1") (pintype "passive"))
      (node (ref "R13") (pin "2") (pinfunction "2_2") (pintype "passive"))
      (node (ref "R15") (pin "1") (pinfunction "1_1") (pintype "passive"))
      (node (ref "R17") (pin "1") (pinfunction "1_1") (pintype "passive"))
      (node (ref "R18") (pin "1") (pinfunction "1_1") (pintype "passive"))
      (node (ref "R2") (pin "1") (pinfunction "1_1") (pintype "passive"))
      (node (ref "R32") (pin "2") (pinfunction "2_2") (pintype "passive"))
      (node (ref "R33") (pin "1") (pinfunction "1_1") (pintype "passive"))
      (node (ref "R37") (pin "1") (pinfunction "1_1") (pintype "passive"))
      (node (ref "R38") (pin "1") (pinfunction "1_1") (pintype "passive"))
      (node (ref "R45") (pin "1") (pinfunction "1_1") (pintype "passive"))
      (node (ref "R46") (pin "2") (pinfunction "2_2") (pintype "passive"))
      (node (ref "R62") (pin "1") (pinfunction "1_1") (pintype "passive"))
      (node (ref "R76") (pin "2") (pinfunction "2_2") (pintype "passive"))
      (node (ref "R78") (pin "1") (pinfunction "1_1") (pintype "passive"))
      (node (ref "R80") (pin "1") (pinfunction "1_1") (pintype "passive"))
      (node (ref "R81") (pin "1") (pinfunction "1_1") (pintype "passive"))
    )
    (net (code "4") (name "Net-(D2-PadC)") (class "Default")
      (node (ref "D2") (pin "C") (pinfunction "C_C") (pintype "passive"))
      (node (ref "D5") (pin "A") (pinfunction "A_A") (pintype "passive"))
    )
    (net (code "5") (name "Net-(D3-PadA)") (class "Default")
      (node (ref "D3") (pin "A") (pinfunction "A_A") (pintype "passive"))
      (node (ref "Q18") (pin "E") (pinfunction "E_E") (pintype "passive"))
      (node (ref "R122") (pin "1") (pinfunction "1_1") (pintype "passive"))
    )
    (net (code "6") (name "Net-(D5-PadC)") (class "Default")
      (node (ref "D5") (pin "C") (pinfunction "C_C") (pintype "passive"))
      (node (ref "Q3") (pin "B") (pinfunction "B_B") (pintype "passive"))
      (node (ref "R7") (pin "2") (pinfunction "2_2") (pintype "passive"))
    )
    (net (code "7") (name "Net-(D6-PadA)") (class "Default")
      (node (ref "D6") (pin "A") (pinfunction "A_A") (pintype "passive"))
      (node (ref "Q4") (pin "B") (pinfunction "B_B") (pintype "passive"))
      (node (ref "R11") (pin "1") (pinfunction "1_1") (pintype "passive"))
    )
    (net (code "8") (name "Net-(D7-PadC)") (class "Default")
      (node (ref "D7") (pin "C") (pinfunction "C_C") (pintype "passive"))
      (node (ref "D8") (pin "A") (pinfunction "A_A") (pintype "passive"))
    )
    (net (code "9") (name "Net-(D18-PadC)") (class "Default")
      (node (ref "D18") (pin "C") (pinfunction "C_C") (pintype "passive"))
      (node (ref "D21") (pin "A") (pinfunction "A_A") (pintype "passive"))
    )
    (net (code "10") (name "Net-(D19-PadA)") (class "Default")
      (node (ref "D19") (pin "A") (pinfunction "A_A") (pintype "passive"))
      (node (ref "Q66") (pin "E") (pinfunction "E_E") (pintype "passive"))
      (node (ref "R73") (pin "1") (pinfunction "1_1") (pintype "passive"))
    )
    (net (code "11") (name "Net-(D21-PadC)") (class "Default")
      (node (ref "D21") (pin "C") (pinfunction "C_C") (pintype "passive"))
      (node (ref "Q80") (pin "B") (pinfunction "B_B") (pintype "passive"))
      (node (ref "R67") (pin "2") (pinfunction "2_2") (pintype "passive"))
    )
    (net (code "12") (name "Net-(D22-PadA)") (class "Default")
      (node (ref "D22") (pin "A") (pinfunction "A_A") (pintype "passive"))
      (node (ref "Q57") (pin "B") (pinfunction "B_B") (pintype "passive"))
      (node (ref "R70") (pin "1") (pinfunction "1_1") (pintype "passive"))
    )
    (net (code "13") (name "Net-(D23-PadC)") (class "Default")
      (node (ref "D23") (pin "C") (pinfunction "C_C") (pintype "passive"))
      (node (ref "D24") (pin "A") (pinfunction "A_A") (pintype "passive"))
    )
    (net (code "14") (name "Net-(IC1A-+IN)") (class "Default")
      (node (ref "C5") (pin "2") (pinfunction "2_2") (pintype "passive"))
      (node (ref "IC1") (pin "3") (pinfunction "+IN_3") (pintype "input"))
      (node (ref "R8") (pin "2") (pinfunction "2_2") (pintype "passive"))
    )
    (net (code "15") (name "Net-(IC1A--IN)") (class "Default")
      (node (ref "C1") (pin "2") (pinfunction "2_2") (pintype "passive"))
      (node (ref "IC1") (pin "2") (pinfunction "-IN_2") (pintype "input"))
      (node (ref "R18") (pin "2") (pinfunction "2_2") (pintype "passive"))
    )
    (net (code "16") (name "Net-(IC1A-OUT)") (class "Default")
      (node (ref "C1") (pin "1") (pinfunction "1_1") (pintype "passive"))
      (node (ref "IC1") (pin "1") (pinfunction "OUT_1") (pintype "output"))
      (node (ref "R10") (pin "1") (pinfunction "1_1") (pintype "passive"))
    )
    (net (code "17") (name "Net-(IC1B-+IN)") (class "Default")
      (node (ref "C6") (pin "2") (pinfunction "2_2") (pintype "passive"))
      (node (ref "IC1") (pin "5") (pinfunction "+IN_5") (pintype "input"))
      (node (ref "R10") (pin "2") (pinfunction "2_2") (pintype "passive"))
    )
    (net (code "18") (name "Net-(IC1B--IN)") (class "Default")
      (node (ref "IC1") (pin "6") (pinfunction "-IN_6") (pintype "input"))
      (node (ref "IC1") (pin "7") (pinfunction "OUT_7") (pintype "output"))
      (node (ref "R19") (pin "1") (pinfunction "1_1") (pintype "passive"))
      (node (ref "R21") (pin "2") (pinfunction "2_2") (pintype "passive"))
    )
    (net (code "19") (name "Net-(IC3A-+IN)") (class "Default")
      (node (ref "C21") (pin "2") (pinfunction "2_2") (pintype "passive"))
      (node (ref "IC3") (pin "3") (pinfunction "+IN_3") (pintype "input"))
      (node (ref "R68") (pin "2") (pinfunction "2_2") (pintype "passive"))
    )
    (net (code "20") (name "Net-(IC3A--IN)") (class "Default")
      (node (ref "C18") (pin "2") (pinfunction "2_2") (pintype "passive"))
      (node (ref "IC3") (pin "2") (pinfunction "-IN_2") (pintype "input"))
      (node (ref "R81") (pin "2") (pinfunction "2_2") (pintype "passive"))
    )
    (net (code "21") (name "Net-(IC3A-OUT)") (class "Default")
      (node (ref "C18") (pin "1") (pinfunction "1_1") (pintype "passive"))
      (node (ref "IC3") (pin "1") (pinfunction "OUT_1") (pintype "output"))
      (node (ref "R92") (pin "1") (pinfunction "1_1") (pintype "passive"))
    )
    (net (code "22") (name "Net-(IC3B-+IN)") (class "Default")
      (node (ref "C22") (pin "2") (pinfunction "2_2") (pintype "passive"))
      (node (ref "IC3") (pin "5") (pinfunction "+IN_5") (pintype "input"))
      (node (ref "R92") (pin "2") (pinfunction "2_2") (pintype "passive"))
    )
    (net (code "23") (name "Net-(IC3B--IN)") (class "Default")
      (node (ref "IC3") (pin "6") (pinfunction "-IN_6") (pintype "input"))
      (node (ref "IC3") (pin "7") (pinfunction "OUT_7") (pintype "output"))
      (node (ref "R82") (pin "1") (pinfunction "1_1") (pintype "passive"))
      (node (ref "R83") (pin "2") (pinfunction "2_2") (pintype "passive"))
    )
    (net (code "24") (name "Net-(LED1-PadC)") (class "Default")
      (node (ref "LED1") (pin "C") (pinfunction "C_C") (pintype "passive"))
      (node (ref "LED4") (pin "C") (pinfunction "C_C") (pintype "passive"))
      (node (ref "R22") (pin "1") (pinfunction "1_1") (pintype "passive"))
      (node (ref "R23") (pin "1") (pinfunction "1_1") (pintype "passive"))
      (node (ref "R44") (pin "1") (pinfunction "1_1") (pintype "passive"))
    )
    (net (code "25") (name "Net-(LED2-PadA)") (class "Default")
      (node (ref "LED2") (pin "A") (pinfunction "A_A") (pintype "passive"))
      (node (ref "LED3") (pin "A") (pinfunction "A_A") (pintype "passive"))
      (node (ref "R35") (pin "2") (pinfunction "2_2") (pintype "passive"))
      (node (ref "R36") (pin "2") (pinfunction "2_2") (pintype "passive"))
      (node (ref "R43") (pin "2") (pinfunction "2_2") (pintype "passive"))
    )
    (net (code "26") (name "Net-(LED2-PadC)") (class "Default")
      (node (ref "LED2") (pin "C") (pinfunction "C_C") (pintype "passive"))
      (node (ref "Q29") (pin "B") (pinfunction "B_B") (pintype "passive"))
      (node (ref "Q40") (pin "B") (pinfunction "B_B") (pintype "passive"))
      (node (ref "R34") (pin "2") (pinfunction "2_2") (pintype "passive"))
    )
    (net (code "27") (name "Net-(LED3-PadC)") (class "Default")
      (node (ref "LED3") (pin "C") (pinfunction "C_C") (pintype "passive"))
      (node (ref "Q36") (pin "B") (pinfunction "B_B") (pintype "passive"))
      (node (ref "R45") (pin "2") (pinfunction "2_2") (pintype "passive"))
    )
    (net (code "28") (name "Net-(Q1-B)") (class "Default")
      (node (ref "D1") (pin "A") (pinfunction "A_A") (pintype "passive"))
      (node (ref "Q1") (pin "1") (pinfunction "B_1") (pintype "passive"))
      (node (ref "Q3") (pin "C") (pinfunction "C_C") (pintype "passive"))
    )
    (net (code "29") (name "Net-(Q1-C)") (class "Default")
      (node (ref "Q1") (pin "3") (pinfunction "C_3") (pintype "passive"))
      (node (ref "Q10") (pin "B") (pinfunction "B_B") (pintype "passive"))
      (node (ref "Q15") (pin "C") (pinfunction "C_C") (pintype "passive"))
    )
    (net (code "30") (name "Net-(Q1-E)") (class "Default")
      (node (ref "Q1") (pin "2") (pinfunction "E_2") (pintype "passive"))
      (node (ref "Q2") (pin "3") (pinfunction "C_3") (pintype "passive"))
    )
    (net (code "31") (name "Net-(Q2-B)") (class "Default")
      (node (ref "D1") (pin "C") (pinfunction "C_C") (pintype "passive"))
      (node (ref "Q2") (pin "1") (pinfunction "B_1") (pintype "passive"))
      (node (ref "R9") (pin "2") (pinfunction "2_2") (pintype "passive"))
    )
    (net (code "32") (name "Net-(Q3-PadE)") (class "Default")
      (node (ref "Q3") (pin "E") (pinfunction "E_E") (pintype "passive"))
      (node (ref "R3") (pin "1") (pinfunction "1_1") (pintype "passive"))
    )
    (net (code "33") (name "Net-(Q4-PadC)") (class "Default")
      (node (ref "Q4") (pin "C") (pinfunction "C_C") (pintype "passive"))
      (node (ref "Q6") (pin "E") (pinfunction "E_E") (pintype "passive"))
    )
    (net (code "34") (name "Net-(Q4-PadE)") (class "Default")
      (node (ref "Q4") (pin "E") (pinfunction "E_E") (pintype "passive"))
      (node (ref "Q9") (pin "C") (pinfunction "C_C") (pintype "passive"))
      (node (ref "R5") (pin "1") (pinfunction "1_1") (pintype "passive"))
    )
    (net (code "35") (name "Net-(Q8-B)") (class "Default")
      (node (ref "D7") (pin "A") (pinfunction "A_A") (pintype "passive"))
      (node (ref "Q8") (pin "1") (pinfunction "B_1") (pintype "passive"))
      (node (ref "R7") (pin "1") (pinfunction "1_1") (pintype "passive"))
    )
    (net (code "36") (name "Net-(Q8-C)") (class "Default")
      (node (ref "D6") (pin "C") (pinfunction "C_C") (pintype "passive"))
      (node (ref "Q6") (pin "B") (pinfunction "B_B") (pintype "passive"))
      (node (ref "Q8") (pin "3") (pinfunction "C_3") (pintype "passive"))
    )
    (net (code "37") (name "Net-(Q8-E)") (class "Default")
      (node (ref "Q8") (pin "2") (pinfunction "E_2") (pintype "passive"))
      (node (ref "R6") (pin "2") (pinfunction "2_2") (pintype "passive"))
    )
    (net (code "38") (name "Net-(Q9-PadE)") (class "Default")
      (node (ref "Q9") (pin "E") (pinfunction "E_E") (pintype "passive"))
      (node (ref "R9") (pin "1") (pinfunction "1_1") (pintype "passive"))
    )
    (net (code "39") (name "Net-(Q10-PadE)") (class "Default")
      (node (ref "Q10") (pin "E") (pinfunction "E_E") (pintype "passive"))
      (node (ref "Q15") (pin "B") (pinfunction "B_B") (pintype "passive"))
      (node (ref "Q18") (pin "B") (pinfunction "B_B") (pintype "passive"))
      (node (ref "Q18") (pin "C") (pinfunction "C_C") (pintype "passive"))
    )
    (net (code "40") (name "Net-(Q11-B)") (class "Default")
      (node (ref "Q11") (pin "1") (pinfunction "B_1") (pintype "passive"))
      (node (ref "Q9") (pin "B") (pinfunction "B_B") (pintype "passive"))
      (node (ref "R17") (pin "2") (pinfunction "2_2") (pintype "passive"))
      (node (ref "R20") (pin "1") (pinfunction "1_1") (pintype "passive"))
    )
    (net (code "41") (name "Net-(Q11-C)") (class "Default")
      (node (ref "Q11") (pin "3") (pinfunction "C_3") (pintype "passive"))
      (node (ref "Q2") (pin "2") (pinfunction "E_2") (pintype "passive"))
      (node (ref "R4") (pin "2") (pinfunction "2_2") (pintype "passive"))
    )
    (net (code "42") (name "Net-(Q11-E)") (class "Default")
      (node (ref "Q11") (pin "2") (pinfunction "E_2") (pintype "passive"))
      (node (ref "R11") (pin "2") (pinfunction "2_2") (pintype "passive"))
    )
    (net (code "43") (name "Net-(Q12-B)") (class "Default")
      (node (ref "Q12") (pin "1") (pinfunction "B_1") (pintype "passive"))
      (node (ref "Q5") (pin "3") (pinfunction "E_3") (pintype "passive"))
      (node (ref "R16") (pin "2") (pinfunction "2_2") (pintype "passive"))
    )
    (net (code "44") (name "Net-(Q12-E)") (class "Default")
      (node (ref "Q12") (pin "3") (pinfunction "E_3") (pintype "passive"))
      (node (ref "Q14") (pin "1") (pinfunction "B_1") (pintype "passive"))
      (node (ref "R12") (pin "2") (pinfunction "2_2") (pintype "passive"))
    )
    (net (code "45") (name "Net-(Q13-B)") (class "Default")
      (node (ref "Q13") (pin "1") (pinfunction "B_1") (pintype "passive"))
      (node (ref "Q17") (pin "3") (pinfunction "E_3") (pintype "passive"))
      (node (ref "R16") (pin "1") (pinfunction "1_1") (pintype "passive"))
    )
    (net (code "46") (name "Net-(Q13-E)") (class "Default")
      (node (ref "Q13") (pin "3") (pinfunction "E_3") (pintype "passive"))
      (node (ref "Q16") (pin "1") (pinfunction "B_1") (pintype "passive"))
      (node (ref "R12") (pin "1") (pinfunction "1_1") (pintype "passive"))
    )
    (net (code "47") (name "Net-(Q14-E)") (class "Default")
      (node (ref "Q14") (pin "3") (pinfunction "E_3") (pintype "passive"))
      (node (ref "R27") (pin "2") (pinfunction "2_2") (pintype "passive"))
    )
    (net (code "48") (name "Net-(Q15-PadE)") (class "Default")
      (node (ref "Q15") (pin "E") (pinfunction "E_E") (pintype "passive"))
      (node (ref "R112") (pin "1") (pinfunction "1_1") (pintype "passive"))
    )
    (net (code "49") (name "Net-(Q16-E)") (class "Default")
      (node (ref "Q16") (pin "3") (pinfunction "E_3") (pintype "passive"))
      (node (ref "R28") (pin "1") (pinfunction "1_1") (pintype "passive"))
    )
    (net (code "50") (name "Net-(Q17-B)") (class "Default")
      (node (ref "C2") (pin "2") (pinfunction "2_2") (pintype "passive"))
      (node (ref "C4") (pin "1") (pinfunction "1_1") (pintype "passive"))
      (node (ref "Q17") (pin "1") (pinfunction "B_1") (pintype "passive"))
      (node (ref "Q21") (pin "3") (pinfunction "E_3") (pintype "passive"))
      (node (ref "Q24") (pin "3") (pinfunction "C_3") (pintype "passive"))
      (node (ref "Q28") (pin "2") (pinfunction "C_2") (pintype "passive"))
      (node (ref "Q28") (pin "4") (pinfunction "C_4") (pintype "passive"))
      (node (ref "R15") (pin "2") (pinfunction "2_2") (pintype "passive"))
      (node (ref "RV1") (pin "1") (pinfunction "A_1") (pintype "passive"))
      (node (ref "RV1") (pin "2") (pinfunction "S_2") (pintype "passive"))
    )
    (net (code "51") (name "Net-(Q19-B)") (class "Default")
      (node (ref "Q19") (pin "1") (pinfunction "B_1") (pintype "passive"))
      (node (ref "Q20") (pin "1") (pinfunction "B_1") (pintype "passive"))
      (node (ref "Q20") (pin "3") (pinfunction "C_3") (pintype "passive"))
      (node (ref "Q7") (pin "2") (pinfunction "E_2") (pintype "passive"))
    )
    (net (code "52") (name "Net-(Q19-C)") (class "Default")
      (node (ref "Q19") (pin "3") (pinfunction "C_3") (pintype "passive"))
      (node (ref "Q6") (pin "C") (pinfunction "C_C") (pintype "passive"))
      (node (ref "Q7") (pin "1") (pinfunction "B_1") (pintype "passive"))
    )
    (net (code "53") (name "Net-(Q19-E)") (class "Default")
      (node (ref "Q19") (pin "2") (pinfunction "E_2") (pintype "passive"))
      (node (ref "R162") (pin "2") (pinfunction "2_2") (pintype "passive"))
    )
    (net (code "54") (name "Net-(Q20-E)") (class "Default")
      (node (ref "D4") (pin "C") (pinfunction "C_C") (pintype "passive"))
      (node (ref "Q20") (pin "2") (pinfunction "E_2") (pintype "passive"))
      (node (ref "R172") (pin "2") (pinfunction "2_2") (pintype "passive"))
    )
    (net (code "55") (name "Net-(Q21-B)") (class "Default")
      (node (ref "Q21") (pin "1") (pinfunction "B_1") (pintype "passive"))
      (node (ref "R30") (pin "1") (pinfunction "1_1") (pintype "passive"))
      (node (ref "RV1") (pin "3") (pinfunction "E_3") (pintype "passive"))
    )
    (net (code "56") (name "Net-(Q21-C)") (class "Default")
      (node (ref "C2") (pin "1") (pinfunction "1_1") (pintype "passive"))
      (node (ref "C3") (pin "2") (pinfunction "2_2") (pintype "passive"))
      (node (ref "Q21") (pin "4") (pinfunction "C_4") (pintype "passive"))
      (node (ref "Q22") (pin "C") (pinfunction "C_C") (pintype "passive"))
      (node (ref "Q27") (pin "2") (pinfunction "C_2") (pintype "passive"))
      (node (ref "Q27") (pin "4") (pinfunction "C_4") (pintype "passive"))
      (node (ref "Q5") (pin "1") (pinfunction "B_1") (pintype "passive"))
      (node (ref "R13") (pin "1") (pinfunction "1_1") (pintype "passive"))
      (node (ref "R30") (pin "2") (pinfunction "2_2") (pintype "passive"))
    )
    (net (code "57") (name "Net-(Q22-PadB)") (class "Default")
      (node (ref "Q22") (pin "B") (pinfunction "B_B") (pintype "passive"))
      (node (ref "Q23") (pin "B") (pinfunction "B_B") (pintype "passive"))
      (node (ref "Q23") (pin "C") (pinfunction "C_C") (pintype "passive"))
      (node (ref "R19") (pin "2") (pinfunction "2_2") (pintype "passive"))
    )
    (net (code "58") (name "Net-(Q22-PadE)") (class "Default")
      (node (ref "Q22") (pin "E") (pinfunction "E_E") (pintype "passive"))
      (node (ref "R24") (pin "1") (pinfunction "1_1") (pintype "passive"))
    )
    (net (code "59") (name "Net-(Q23-PadE)") (class "Default")
      (node (ref "Q23") (pin "E") (pinfunction "E_E") (pintype "passive"))
      (node (ref "R25") (pin "1") (pinfunction "1_1") (pintype "passive"))
    )
    (net (code "60") (name "Net-(Q24-B)") (class "Default")
      (node (ref "Q24") (pin "1") (pinfunction "B_1") (pintype "passive"))
      (node (ref "Q25") (pin "1") (pinfunction "B_1") (pintype "passive"))
      (node (ref "Q25") (pin "3") (pinfunction "C_3") (pintype "passive"))
      (node (ref "R21") (pin "1") (pinfunction "1_1") (pintype "passive"))
    )
    (net (code "61") (name "Net-(Q24-E)") (class "Default")
      (node (ref "Q24") (pin "2") (pinfunction "E_2") (pintype "passive"))
      (node (ref "R26") (pin "2") (pinfunction "2_2") (pintype "passive"))
    )
    (net (code "62") (name "Net-(Q25-E)") (class "Default")
      (node (ref "Q25") (pin "2") (pinfunction "E_2") (pintype "passive"))
      (node (ref "R31") (pin "2") (pinfunction "2_2") (pintype "passive"))
    )
    (net (code "63") (name "Net-(Q26-B)") (class "Default")
      (node (ref "LED4") (pin "A") (pinfunction "A_A") (pintype "passive"))
      (node (ref "Q26") (pin "1") (pinfunction "B_1") (pintype "passive"))
      (node (ref "R46") (pin "1") (pinfunction "1_1") (pintype "passive"))
    )
    (net (code "64") (name "Net-(Q26-C)") (class "Default")
      (node (ref "Q26") (pin "3") (pinfunction "C_3") (pintype "passive"))
      (node (ref "R39") (pin "1") (pinfunction "1_1") (pintype "passive"))
      (node (ref "R40") (pin "1") (pinfunction "1_1") (pintype "passive"))
    )
    (net (code "65") (name "Net-(Q26-E)") (class "Default")
      (node (ref "Q26") (pin "2") (pinfunction "E_2") (pintype "passive"))
      (node (ref "R44") (pin "2") (pinfunction "2_2") (pintype "passive"))
    )
    (net (code "66") (name "Net-(Q27-B)") (class "Default")
      (node (ref "D3") (pin "C") (pinfunction "C_C") (pintype "passive"))
      (node (ref "Q27") (pin "1") (pinfunction "B_1") (pintype "passive"))
      (node (ref "R14") (pin "2") (pinfunction "2_2") (pintype "passive"))
    )
    (net (code "67") (name "Net-(Q27-E)") (class "Default")
      (node (ref "Q10") (pin "C") (pinfunction "C_C") (pintype "passive"))
      (node (ref "Q27") (pin "3") (pinfunction "E_3") (pintype "passive"))
    )
    (net (code "68") (name "Net-(Q28-B)") (class "Default")
      (node (ref "D4") (pin "A") (pinfunction "A_A") (pintype "passive"))
      (node (ref "Q28") (pin "1") (pinfunction "B_1") (pintype "passive"))
      (node (ref "R14") (pin "1") (pinfunction "1_1") (pintype "passive"))
    )
    (net (code "69") (name "Net-(Q28-E)") (class "Default")
      (node (ref "Q28") (pin "3") (pinfunction "E_3") (pintype "passive"))
      (node (ref "Q7") (pin "3") (pinfunction "C_3") (pintype "passive"))
    )
    (net (code "70") (name "Net-(Q29-PadE)") (class "Default")
      (node (ref "Q29") (pin "E") (pinfunction "E_E") (pintype "passive"))
      (node (ref "R35") (pin "1") (pinfunction "1_1") (pintype "passive"))
    )
    (net (code "71") (name "Net-(Q30-B)") (class "Default")
      (node (ref "LED1") (pin "A") (pinfunction "A_A") (pintype "passive"))
      (node (ref "Q30") (pin "1") (pinfunction "B_1") (pintype "passive"))
      (node (ref "Q31") (pin "1") (pinfunction "B_1") (pintype "passive"))
      (node (ref "R29") (pin "1") (pinfunction "1_1") (pintype "passive"))
    )
    (net (code "72") (name "Net-(Q30-C)") (class "Default")
      (node (ref "Q30") (pin "3") (pinfunction "C_3") (pintype "passive"))
      (node (ref "Q35") (pin "C") (pinfunction "C_C") (pintype "passive"))
      (node (ref "Q37") (pin "2") (pinfunction "E_2") (pintype "passive"))
    )
    (net (code "73") (name "Net-(Q30-E)") (class "Default")
      (node (ref "Q30") (pin "2") (pinfunction "E_2") (pintype "passive"))
      (node (ref "R22") (pin "2") (pinfunction "2_2") (pintype "passive"))
    )
    (net (code "74") (name "Net-(Q31-C)") (class "Default")
      (node (ref "Q31") (pin "3") (pinfunction "C_3") (pintype "passive"))
      (node (ref "Q32") (pin "2") (pinfunction "E_2") (pintype "passive"))
      (node (ref "Q34") (pin "C") (pinfunction "C_C") (pintype "passive"))
    )
    (net (code "75") (name "Net-(Q31-E)") (class "Default")
      (node (ref "Q31") (pin "2") (pinfunction "E_2") (pintype "passive"))
      (node (ref "R23") (pin "2") (pinfunction "2_2") (pintype "passive"))
    )
    (net (code "76") (name "Net-(Q32-B)") (class "Default")
      (node (ref "Q32") (pin "1") (pinfunction "B_1") (pintype "passive"))
      (node (ref "Q37") (pin "1") (pinfunction "B_1") (pintype "passive"))
      (node (ref "R29") (pin "2") (pinfunction "2_2") (pintype "passive"))
      (node (ref "R32") (pin "1") (pinfunction "1_1") (pintype "passive"))
    )
    (net (code "77") (name "Net-(Q32-C)") (class "Default")
      (node (ref "Q32") (pin "3") (pinfunction "C_3") (pintype "passive"))
      (node (ref "Q41") (pin "C") (pinfunction "C_C") (pintype "passive"))
      (node (ref "R38") (pin "2") (pinfunction "2_2") (pintype "passive"))
    )
    (net (code "78") (name "Net-(Q33-PadB)") (class "Default")
      (node (ref "Q33") (pin "B") (pinfunction "B_B") (pintype "passive"))
      (node (ref "Q41") (pin "B") (pinfunction "B_B") (pintype "passive"))
      (node (ref "R33") (pin "2") (pinfunction "2_2") (pintype "passive"))
      (node (ref "R34") (pin "1") (pinfunction "1_1") (pintype "passive"))
    )
    (net (code "79") (name "Net-(Q34-PadE)") (class "Default")
      (node (ref "Q34") (pin "E") (pinfunction "E_E") (pintype "passive"))
      (node (ref "R42") (pin "1") (pinfunction "1_1") (pintype "passive"))
    )
    (net (code "80") (name "Net-(Q35-PadE)") (class "Default")
      (node (ref "Q35") (pin "E") (pinfunction "E_E") (pintype "passive"))
      (node (ref "R41") (pin "1") (pinfunction "1_1") (pintype "passive"))
    )
    (net (code "81") (name "Net-(Q36-PadC)") (class "Default")
      (node (ref "Q36") (pin "C") (pinfunction "C_C") (pintype "passive"))
      (node (ref "R41") (pin "2") (pinfunction "2_2") (pintype "passive"))
      (node (ref "R42") (pin "2") (pinfunction "2_2") (pintype "passive"))
    )
    (net (code "82") (name "Net-(Q36-PadE)") (class "Default")
      (node (ref "Q36") (pin "E") (pinfunction "E_E") (pintype "passive"))
      (node (ref "R43") (pin "1") (pinfunction "1_1") (pintype "passive"))
    )
    (net (code "83") (name "Net-(Q37-C)") (class "Default")
      (node (ref "Q33") (pin "C") (pinfunction "C_C") (pintype "passive"))
      (node (ref "Q37") (pin "3") (pinfunction "C_3") (pintype "passive"))
      (node (ref "R37") (pin "2") (pinfunction "2_2") (pintype "passive"))
    )
    (net (code "84") (name "Net-(Q38-B)") (class "Default")
      (node (ref "Q34") (pin "B") (pinfunction "B_B") (pintype "passive"))
      (node (ref "Q38") (pin "1") (pinfunction "B_1") (pintype "passive"))
      (node (ref "R47") (pin "2") (pinfunction "2_2") (pintype "passive"))
    )
    (net (code "85") (name "Net-(Q38-C)") (class "Default")
      (node (ref "Q38") (pin "3") (pinfunction "C_3") (pintype "passive"))
      (node (ref "Q40") (pin "C") (pinfunction "C_C") (pintype "passive"))
      (node (ref "Q41") (pin "E") (pinfunction "E_E") (pintype "passive"))
    )
    (net (code "86") (name "Net-(Q38-E)") (class "Default")
      (node (ref "Q38") (pin "2") (pinfunction "E_2") (pintype "passive"))
      (node (ref "R40") (pin "2") (pinfunction "2_2") (pintype "passive"))
    )
    (net (code "87") (name "Net-(Q39-B)") (class "Default")
      (node (ref "Q35") (pin "B") (pinfunction "B_B") (pintype "passive"))
      (node (ref "Q39") (pin "1") (pinfunction "B_1") (pintype "passive"))
      (node (ref "R48") (pin "2") (pinfunction "2_2") (pintype "passive"))
    )
    (net (code "88") (name "Net-(Q39-C)") (class "Default")
      (node (ref "Q29") (pin "C") (pinfunction "C_C") (pintype "passive"))
      (node (ref "Q33") (pin "E") (pinfunction "E_E") (pintype "passive"))
      (node (ref "Q39") (pin "3") (pinfunction "C_3") (pintype "passive"))
    )
    (net (code "89") (name "Net-(Q39-E)") (class "Default")
      (node (ref "Q39") (pin "2") (pinfunction "E_2") (pintype "passive"))
      (node (ref "R39") (pin "2") (pinfunction "2_2") (pintype "passive"))
    )
    (net (code "90") (name "Net-(Q40-PadE)") (class "Default")
      (node (ref "Q40") (pin "E") (pinfunction "E_E") (pintype "passive"))
      (node (ref "R36") (pin "1") (pinfunction "1_1") (pintype "passive"))
    )
    (net (code "91") (name "Net-(Q55-B)") (class "Default")
      (node (ref "D17") (pin "A") (pinfunction "A_A") (pintype "passive"))
      (node (ref "Q55") (pin "1") (pinfunction "B_1") (pintype "passive"))
      (node (ref "Q80") (pin "C") (pinfunction "C_C") (pintype "passive"))
    )
    (net (code "92") (name "Net-(Q55-C)") (class "Default")
      (node (ref "Q55") (pin "3") (pinfunction "C_3") (pintype "passive"))
      (node (ref "Q63") (pin "B") (pinfunction "B_B") (pintype "passive"))
      (node (ref "Q65") (pin "C") (pinfunction "C_C") (pintype "passive"))
    )
    (net (code "93") (name "Net-(Q55-E)") (class "Default")
      (node (ref "Q55") (pin "2") (pinfunction "E_2") (pintype "passive"))
      (node (ref "Q56") (pin "3") (pinfunction "C_3") (pintype "passive"))
    )
    (net (code "94") (name "Net-(Q56-B)") (class "Default")
      (node (ref "D17") (pin "C") (pinfunction "C_C") (pintype "passive"))
      (node (ref "Q56") (pin "1") (pinfunction "B_1") (pintype "passive"))
      (node (ref "R69") (pin "2") (pinfunction "2_2") (pintype "passive"))
    )
    (net (code "95") (name "Net-(Q56-E)") (class "Default")
      (node (ref "Q56") (pin "2") (pinfunction "E_2") (pintype "passive"))
      (node (ref "Q64") (pin "3") (pinfunction "C_3") (pintype "passive"))
      (node (ref "R64") (pin "2") (pinfunction "2_2") (pintype "passive"))
    )
    (net (code "96") (name "Net-(Q57-PadC)") (class "Default")
      (node (ref "Q57") (pin "C") (pinfunction "C_C") (pintype "passive"))
      (node (ref "Q58") (pin "E") (pinfunction "E_E") (pintype "passive"))
    )
    (net (code "97") (name "Net-(Q57-PadE)") (class "Default")
      (node (ref "Q57") (pin "E") (pinfunction "E_E") (pintype "passive"))
      (node (ref "Q62") (pin "C") (pinfunction "C_C") (pintype "passive"))
      (node (ref "R65") (pin "1") (pinfunction "1_1") (pintype "passive"))
    )
    (net (code "98") (name "Net-(Q59-B)") (class "Default")
      (node (ref "C17") (pin "1") (pinfunction "1_1") (pintype "passive"))
      (node (ref "C19") (pin "2") (pinfunction "2_2") (pintype "passive"))
      (node (ref "Q59") (pin "1") (pinfunction "B_1") (pintype "passive"))
      (node (ref "Q67") (pin "2") (pinfunction "C_2") (pintype "passive"))
      (node (ref "Q67") (pin "4") (pinfunction "C_4") (pintype "passive"))
      (node (ref "Q74") (pin "4") (pinfunction "C_4") (pintype "passive"))
      (node (ref "Q75") (pin "C") (pinfunction "C_C") (pintype "passive"))
      (node (ref "R76") (pin "1") (pinfunction "1_1") (pintype "passive"))
      (node (ref "R90") (pin "2") (pinfunction "2_2") (pintype "passive"))
    )
    (net (code "99") (name "Net-(Q59-E)") (class "Default")
      (node (ref "Q59") (pin "3") (pinfunction "E_3") (pintype "passive"))
      (node (ref "Q68") (pin "1") (pinfunction "B_1") (pintype "passive"))
      (node (ref "R79") (pin "2") (pinfunction "2_2") (pintype "passive"))
    )
    (net (code "100") (name "Net-(Q60-B)") (class "Default")
      (node (ref "C17") (pin "2") (pinfunction "2_2") (pintype "passive"))
      (node (ref "C20") (pin "1") (pinfunction "1_1") (pintype "passive"))
      (node (ref "Q60") (pin "1") (pinfunction "B_1") (pintype "passive"))
      (node (ref "Q74") (pin "3") (pinfunction "E_3") (pintype "passive"))
      (node (ref "Q77") (pin "3") (pinfunction "C_3") (pintype "passive"))
      (node (ref "Q79") (pin "2") (pinfunction "C_2") (pintype "passive"))
      (node (ref "Q79") (pin "4") (pinfunction "C_4") (pintype "passive"))
      (node (ref "R78") (pin "2") (pinfunction "2_2") (pintype "passive"))
      (node (ref "RV3") (pin "1") (pinfunction "A_1") (pintype "passive"))
      (node (ref "RV3") (pin "2") (pinfunction "S_2") (pintype "passive"))
    )
    (net (code "101") (name "Net-(Q60-E)") (class "Default")
      (node (ref "Q60") (pin "3") (pinfunction "E_3") (pintype "passive"))
      (node (ref "Q69") (pin "1") (pinfunction "B_1") (pintype "passive"))
      (node (ref "R79") (pin "1") (pinfunction "1_1") (pintype "passive"))
    )
    (net (code "102") (name "Net-(Q61-B)") (class "Default")
      (node (ref "Q58") (pin "C") (pinfunction "C_C") (pintype "passive"))
      (node (ref "Q61") (pin "1") (pinfunction "B_1") (pintype "passive"))
      (node (ref "Q72") (pin "3") (pinfunction "C_3") (pintype "passive"))
    )
    (net (code "103") (name "Net-(Q61-C)") (class "Default")
      (node (ref "Q61") (pin "3") (pinfunction "C_3") (pintype "passive"))
      (node (ref "Q79") (pin "3") (pinfunction "E_3") (pintype "passive"))
    )
    (net (code "104") (name "Net-(Q61-E)") (class "Default")
      (node (ref "Q61") (pin "2") (pinfunction "E_2") (pintype "passive"))
      (node (ref "Q72") (pin "1") (pinfunction "B_1") (pintype "passive"))
      (node (ref "Q73") (pin "1") (pinfunction "B_1") (pintype "passive"))
      (node (ref "Q73") (pin "3") (pinfunction "C_3") (pintype "passive"))
    )
    (net (code "105") (name "Net-(Q62-PadE)") (class "Default")
      (node (ref "Q62") (pin "E") (pinfunction "E_E") (pintype "passive"))
      (node (ref "R69") (pin "1") (pinfunction "1_1") (pintype "passive"))
    )
    (net (code "106") (name "Net-(Q63-PadE)") (class "Default")
      (node (ref "Q63") (pin "E") (pinfunction "E_E") (pintype "passive"))
      (node (ref "Q65") (pin "B") (pinfunction "B_B") (pintype "passive"))
      (node (ref "Q66") (pin "B") (pinfunction "B_B") (pintype "passive"))
      (node (ref "Q66") (pin "C") (pinfunction "C_C") (pintype "passive"))
    )
    (net (code "107") (name "Net-(Q64-B)") (class "Default")
      (node (ref "Q62") (pin "B") (pinfunction "B_B") (pintype "passive"))
      (node (ref "Q64") (pin "1") (pinfunction "B_1") (pintype "passive"))
      (node (ref "R80") (pin "2") (pinfunction "2_2") (pintype "passive"))
      (node (ref "R91") (pin "1") (pinfunction "1_1") (pintype "passive"))
    )
    (net (code "108") (name "Net-(Q64-E)") (class "Default")
      (node (ref "Q64") (pin "2") (pinfunction "E_2") (pintype "passive"))
      (node (ref "R70") (pin "2") (pinfunction "2_2") (pintype "passive"))
    )
    (net (code "109") (name "Net-(Q65-PadE)") (class "Default")
      (node (ref "Q65") (pin "E") (pinfunction "E_E") (pintype "passive"))
      (node (ref "R72") (pin "1") (pinfunction "1_1") (pintype "passive"))
    )
    (net (code "110") (name "Net-(Q67-B)") (class "Default")
      (node (ref "D19") (pin "C") (pinfunction "C_C") (pintype "passive"))
      (node (ref "Q67") (pin "1") (pinfunction "B_1") (pintype "passive"))
      (node (ref "R77") (pin "2") (pinfunction "2_2") (pintype "passive"))
    )
    (net (code "111") (name "Net-(Q67-E)") (class "Default")
      (node (ref "Q63") (pin "C") (pinfunction "C_C") (pintype "passive"))
      (node (ref "Q67") (pin "3") (pinfunction "E_3") (pintype "passive"))
    )
    (net (code "112") (name "Net-(Q68-E)") (class "Default")
      (node (ref "Q68") (pin "3") (pinfunction "E_3") (pintype "passive"))
      (node (ref "Q70") (pin "1") (pinfunction "B_1") (pintype "passive"))
      (node (ref "R71") (pin "2") (pinfunction "2_2") (pintype "passive"))
    )
    (net (code "113") (name "Net-(Q69-E)") (class "Default")
      (node (ref "Q69") (pin "3") (pinfunction "E_3") (pintype "passive"))
      (node (ref "Q71") (pin "1") (pinfunction "B_1") (pintype "passive"))
      (node (ref "R71") (pin "1") (pinfunction "1_1") (pintype "passive"))
    )
    (net (code "114") (name "Net-(Q70-E)") (class "Default")
      (node (ref "Q70") (pin "3") (pinfunction "E_3") (pintype "passive"))
      (node (ref "R87") (pin "2") (pinfunction "2_2") (pintype "passive"))
    )
    (net (code "115") (name "Net-(Q71-E)") (class "Default")
      (node (ref "Q71") (pin "3") (pinfunction "E_3") (pintype "passive"))
      (node (ref "R88") (pin "1") (pinfunction "1_1") (pintype "passive"))
    )
    (net (code "116") (name "Net-(Q72-E)") (class "Default")
      (node (ref "Q72") (pin "2") (pinfunction "E_2") (pintype "passive"))
      (node (ref "R74") (pin "2") (pinfunction "2_2") (pintype "passive"))
    )
    (net (code "117") (name "Net-(Q73-E)") (class "Default")
      (node (ref "D20") (pin "C") (pinfunction "C_C") (pintype "passive"))
      (node (ref "Q73") (pin "2") (pinfunction "E_2") (pintype "passive"))
      (node (ref "R75") (pin "2") (pinfunction "2_2") (pintype "passive"))
    )
    (net (code "118") (name "Net-(Q74-B)") (class "Default")
      (node (ref "Q74") (pin "1") (pinfunction "B_1") (pintype "passive"))
      (node (ref "R90") (pin "1") (pinfunction "1_1") (pintype "passive"))
      (node (ref "RV3") (pin "3") (pinfunction "E_3") (pintype "passive"))
    )
    (net (code "119") (name "Net-(Q75-PadB)") (class "Default")
      (node (ref "Q75") (pin "B") (pinfunction "B_B") (pintype "passive"))
      (node (ref "Q76") (pin "B") (pinfunction "B_B") (pintype "passive"))
      (node (ref "Q76") (pin "C") (pinfunction "C_C") (pintype "passive"))
      (node (ref "R82") (pin "2") (pinfunction "2_2") (pintype "passive"))
    )
    (net (code "120") (name "Net-(Q75-PadE)") (class "Default")
      (node (ref "Q75") (pin "E") (pinfunction "E_E") (pintype "passive"))
      (node (ref "R84") (pin "1") (pinfunction "1_1") (pintype "passive"))
    )
    (net (code "121") (name "Net-(Q76-PadE)") (class "Default")
      (node (ref "Q76") (pin "E") (pinfunction "E_E") (pintype "passive"))
      (node (ref "R85") (pin "1") (pinfunction "1_1") (pintype "passive"))
    )
    (net (code "122") (name "Net-(Q77-B)") (class "Default")
      (node (ref "Q77") (pin "1") (pinfunction "B_1") (pintype "passive"))
      (node (ref "Q78") (pin "1") (pinfunction "B_1") (pintype "passive"))
      (node (ref "Q78") (pin "3") (pinfunction "C_3") (pintype "passive"))
      (node (ref "R83") (pin "1") (pinfunction "1_1") (pintype "passive"))
    )
    (net (code "123") (name "Net-(Q77-E)") (class "Default")
      (node (ref "Q77") (pin "2") (pinfunction "E_2") (pintype "passive"))
      (node (ref "R86") (pin "2") (pinfunction "2_2") (pintype "passive"))
    )
    (net (code "124") (name "Net-(Q78-E)") (class "Default")
      (node (ref "Q78") (pin "2") (pinfunction "E_2") (pintype "passive"))
      (node (ref "R89") (pin "2") (pinfunction "2_2") (pintype "passive"))
    )
    (net (code "125") (name "Net-(Q79-B)") (class "Default")
      (node (ref "D20") (pin "A") (pinfunction "A_A") (pintype "passive"))
      (node (ref "Q79") (pin "1") (pinfunction "B_1") (pintype "passive"))
      (node (ref "R77") (pin "1") (pinfunction "1_1") (pintype "passive"))
    )
    (net (code "126") (name "Net-(Q80-PadE)") (class "Default")
      (node (ref "Q80") (pin "E") (pinfunction "E_E") (pintype "passive"))
      (node (ref "R63") (pin "1") (pinfunction "1_1") (pintype "passive"))
    )
    (net (code "127") (name "Net-(Q81-B)") (class "Default")
      (node (ref "D23") (pin "A") (pinfunction "A_A") (pintype "passive"))
      (node (ref "Q81") (pin "1") (pinfunction "B_1") (pintype "passive"))
      (node (ref "R67") (pin "1") (pinfunction "1_1") (pintype "passive"))
    )
    (net (code "128") (name "Net-(Q81-C)") (class "Default")
      (node (ref "D22") (pin "C") (pinfunction "C_C") (pintype "passive"))
      (node (ref "Q58") (pin "B") (pinfunction "B_B") (pintype "passive"))
      (node (ref "Q81") (pin "3") (pinfunction "C_3") (pintype "passive"))
    )
    (net (code "129") (name "Net-(Q81-E)") (class "Default")
      (node (ref "Q81") (pin "2") (pinfunction "E_2") (pintype "passive"))
      (node (ref "R66") (pin "2") (pinfunction "2_2") (pintype "passive"))
    )
    (net (code "130") (name "Net-(R1-Pad1)") (class "Default")
      (node (ref "R1") (pin "1") (pinfunction "1_1") (pintype "passive"))
      (node (ref "R2") (pin "2") (pinfunction "2_2") (pintype "passive"))
      (node (ref "R4") (pin "1") (pinfunction "1_1") (pintype "passive"))
      (node (ref "R5") (pin "2") (pinfunction "2_2") (pintype "passive"))
    )
    (net (code "131") (name "Net-(R1-Pad2)") (class "Default")
      (node (ref "R1") (pin "2") (pinfunction "2_2") (pintype "passive"))
      (node (ref "R27") (pin "1") (pinfunction "1_1") (pintype "passive"))
      (node (ref "R28") (pin "2") (pinfunction "2_2") (pintype "passive"))
      (node (ref "R8") (pin "1") (pinfunction "1_1") (pintype "passive"))
    )
    (net (code "132") (name "Net-(R61-Pad1)") (class "Default")
      (node (ref "R61") (pin "1") (pinfunction "1_1") (pintype "passive"))
      (node (ref "R62") (pin "2") (pinfunction "2_2") (pintype "passive"))
      (node (ref "R64") (pin "1") (pinfunction "1_1") (pintype "passive"))
      (node (ref "R65") (pin "2") (pinfunction "2_2") (pintype "passive"))
    )
    (net (code "133") (name "Net-(R61-Pad2)") (class "Default")
      (node (ref "R61") (pin "2") (pinfunction "2_2") (pintype "passive"))
      (node (ref "R68") (pin "1") (pinfunction "1_1") (pintype "passive"))
      (node (ref "R87") (pin "1") (pinfunction "1_1") (pintype "passive"))
      (node (ref "R88") (pin "2") (pinfunction "2_2") (pintype "passive"))
    )
    (net (code "134") (name "unconnected-(R20-Pad2)") (class "Default")
      (node (ref "R20") (pin "2") (pinfunction "2_2") (pintype "passive"))
    )
    (net (code "135") (name "unconnected-(R47-Pad1)") (class "Default")
      (node (ref "R47") (pin "1") (pinfunction "1_1") (pintype "passive"))
    )
    (net (code "136") (name "unconnected-(R48-Pad1)") (class "Default")
      (node (ref "R48") (pin "1") (pinfunction "1_1") (pintype "passive"))
    )
    (net (code "137") (name "unconnected-(R91-Pad2)") (class "Default")
      (node (ref "R91") (pin "2") (pinfunction "2_2") (pintype "passive"))
    )
  )
)
